# Easy_RFPA_RevC.net
KiCad netlist of a schematic drawn in EAGLE
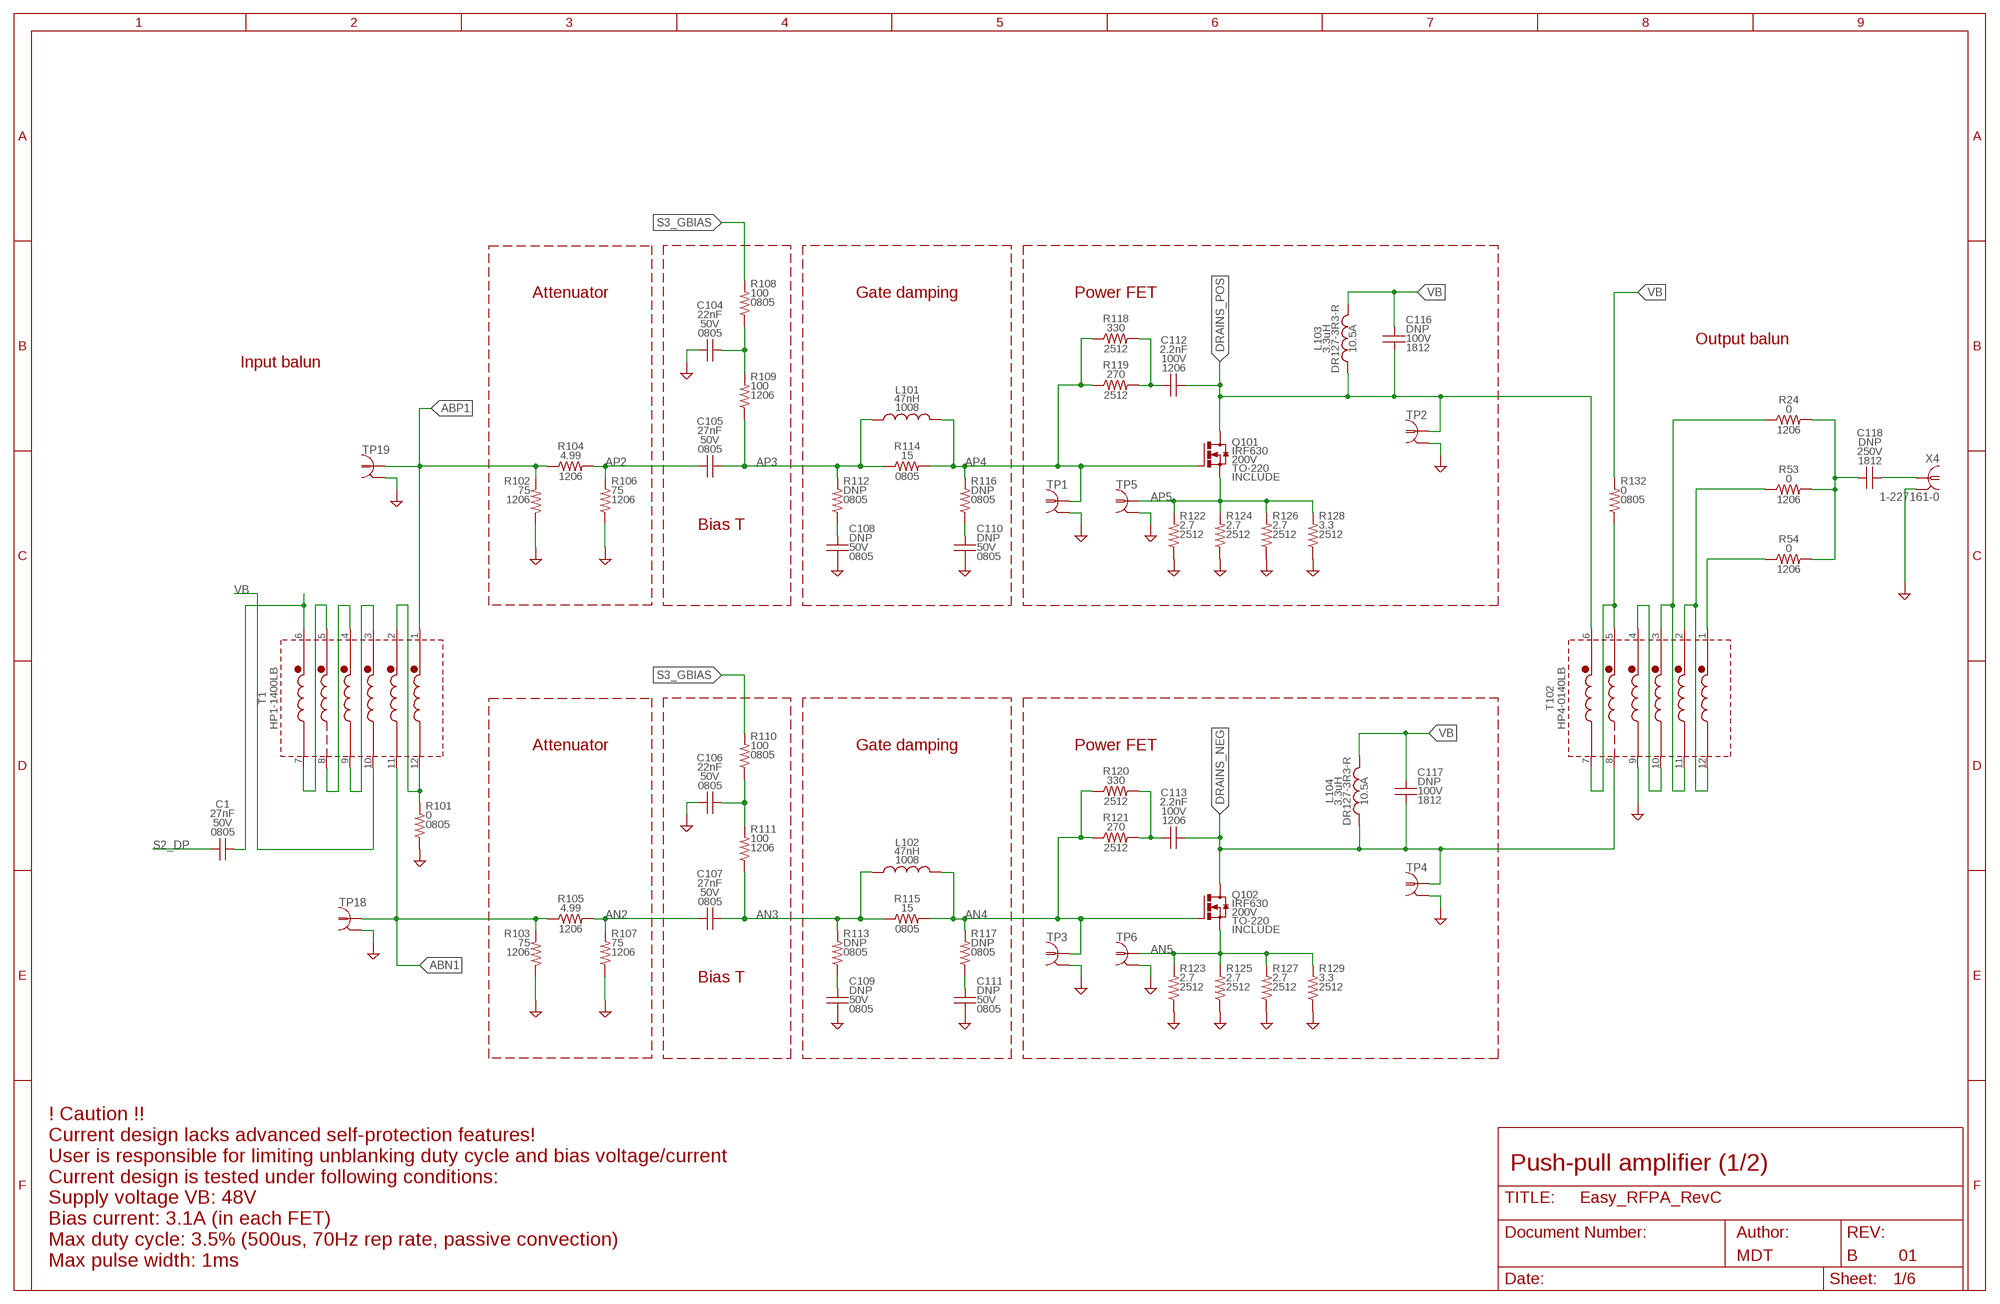
[diagram p0: schematic, sheet 1]
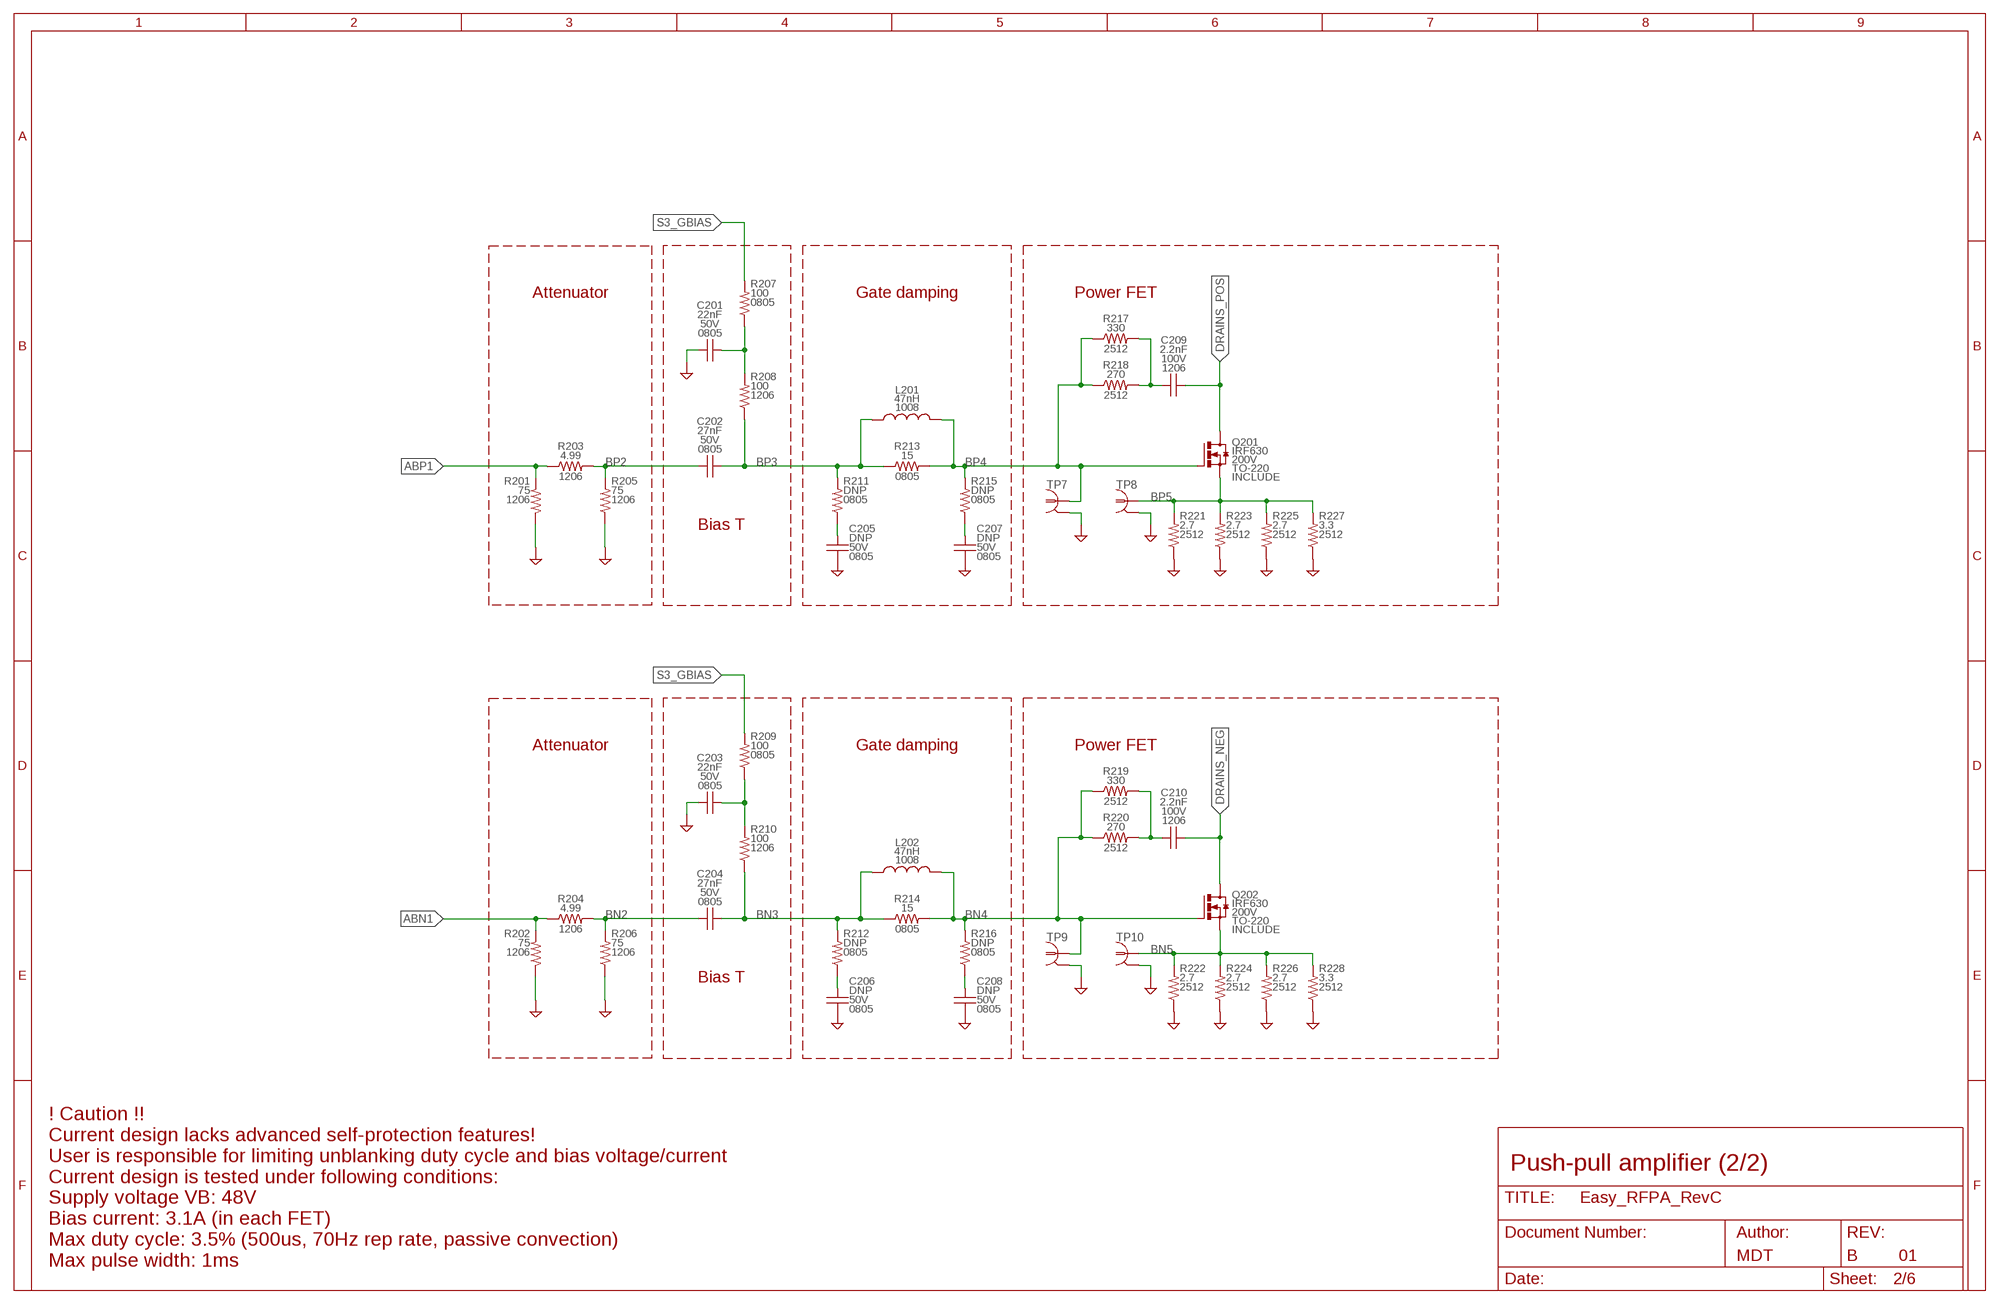
[diagram p1: schematic, sheet 2]
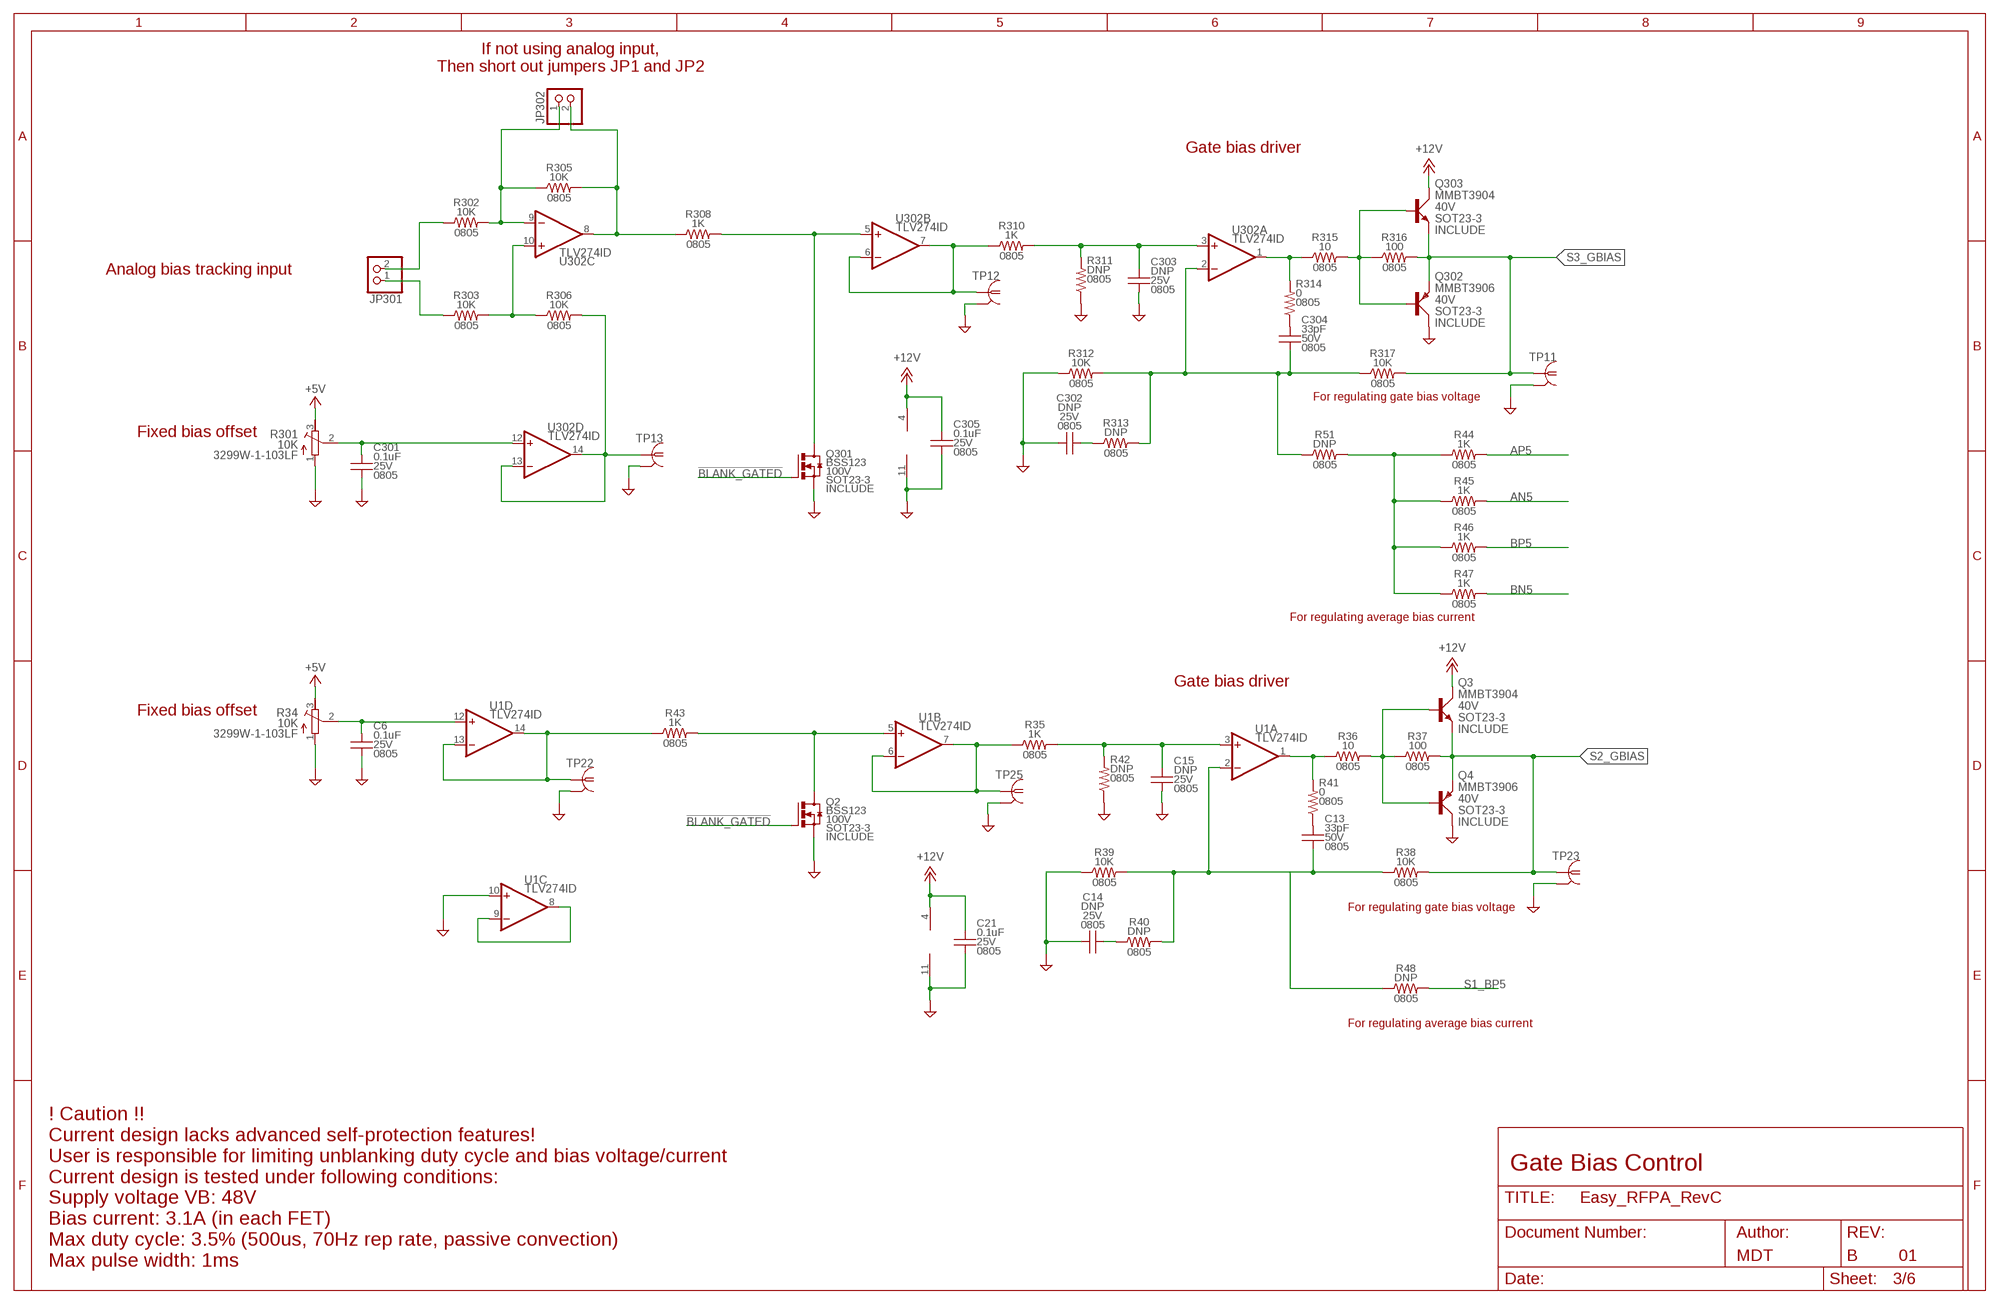
[diagram p2: schematic, sheet 3]
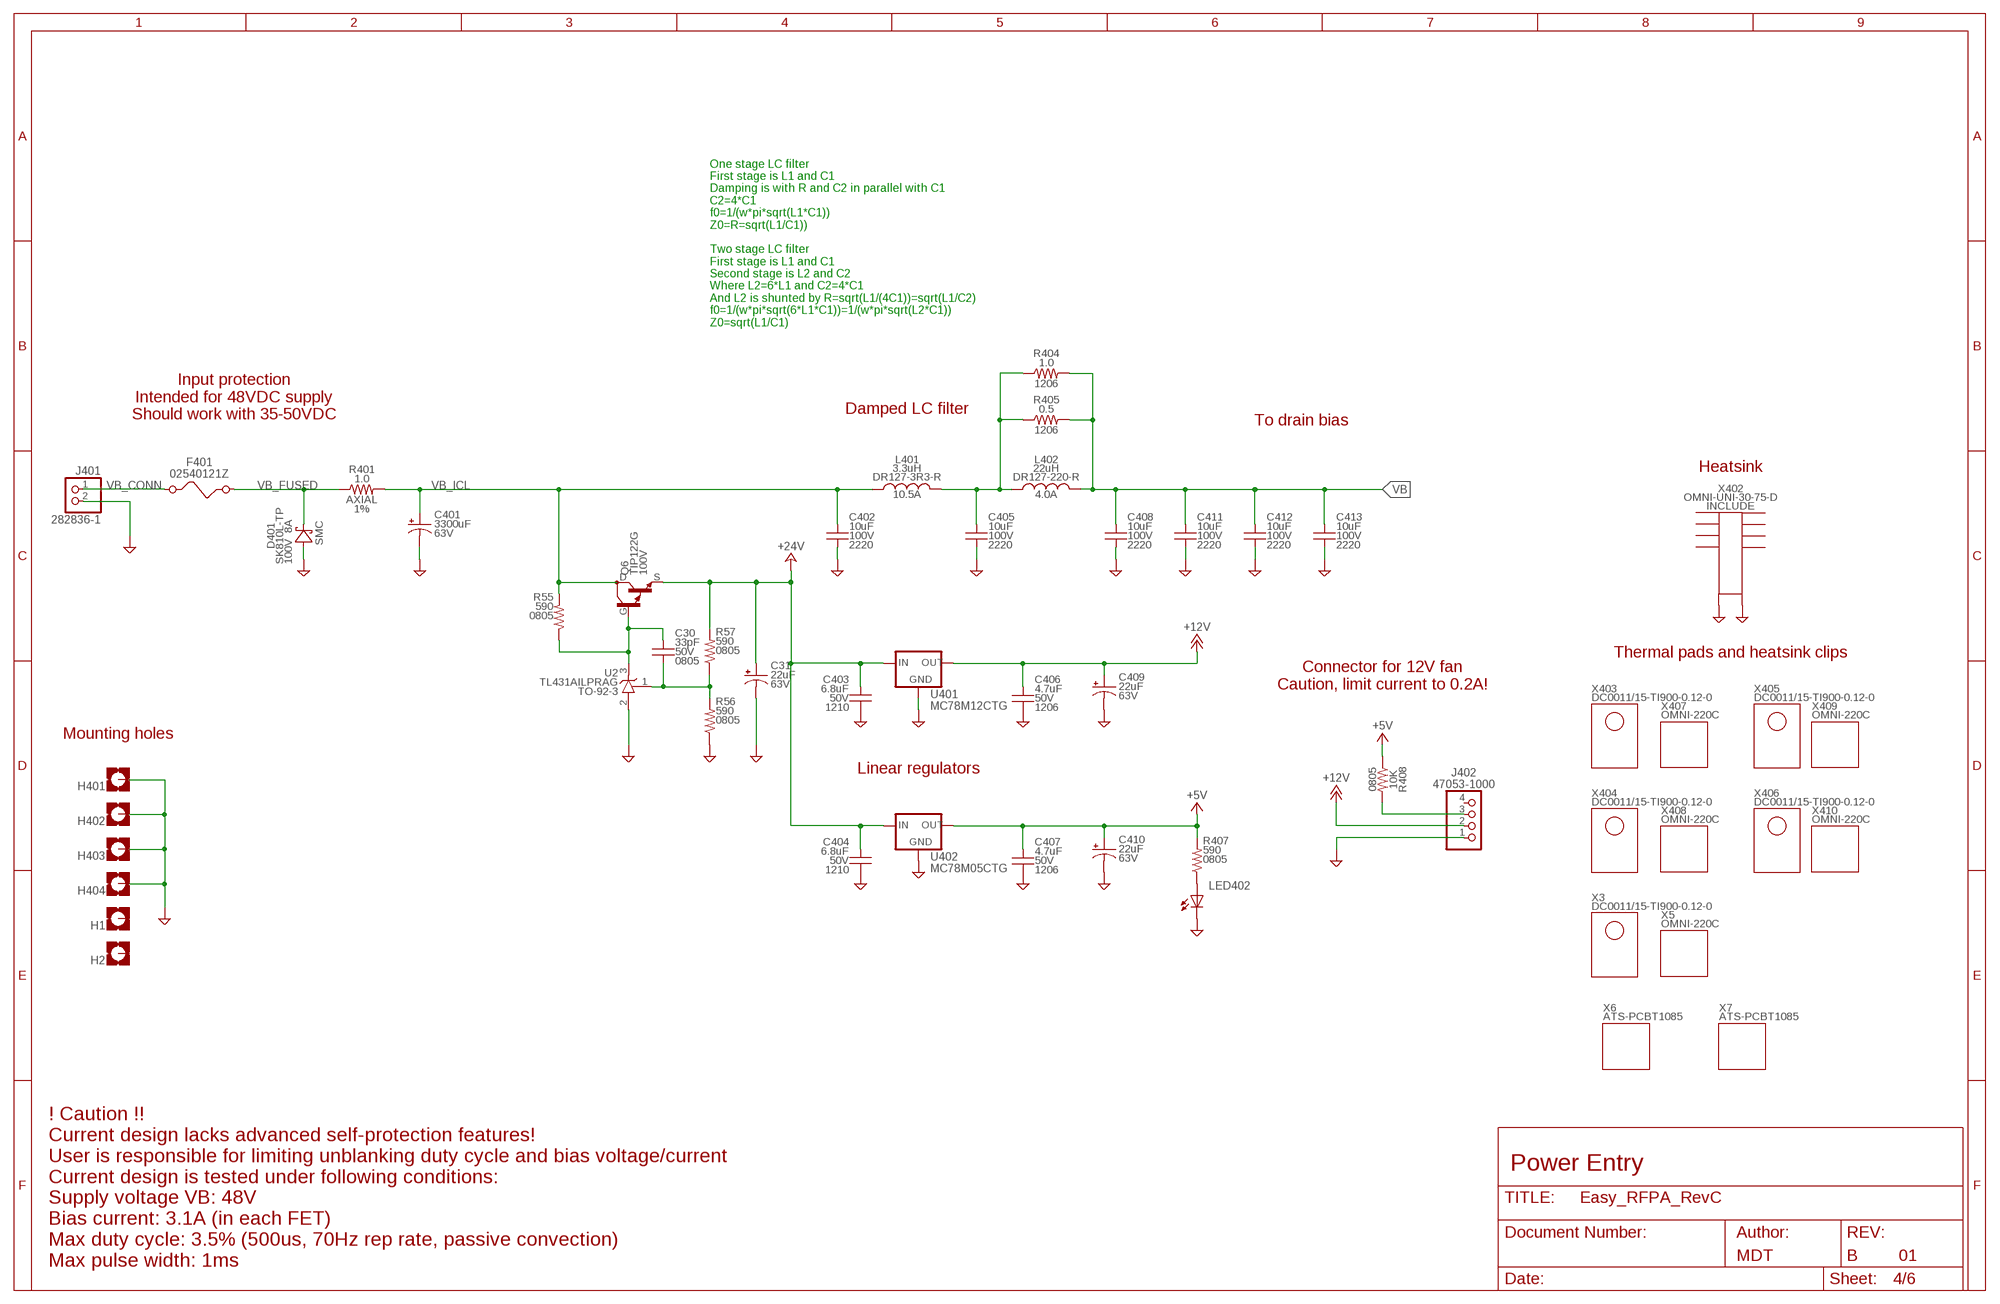
[diagram p3: schematic, sheet 4]
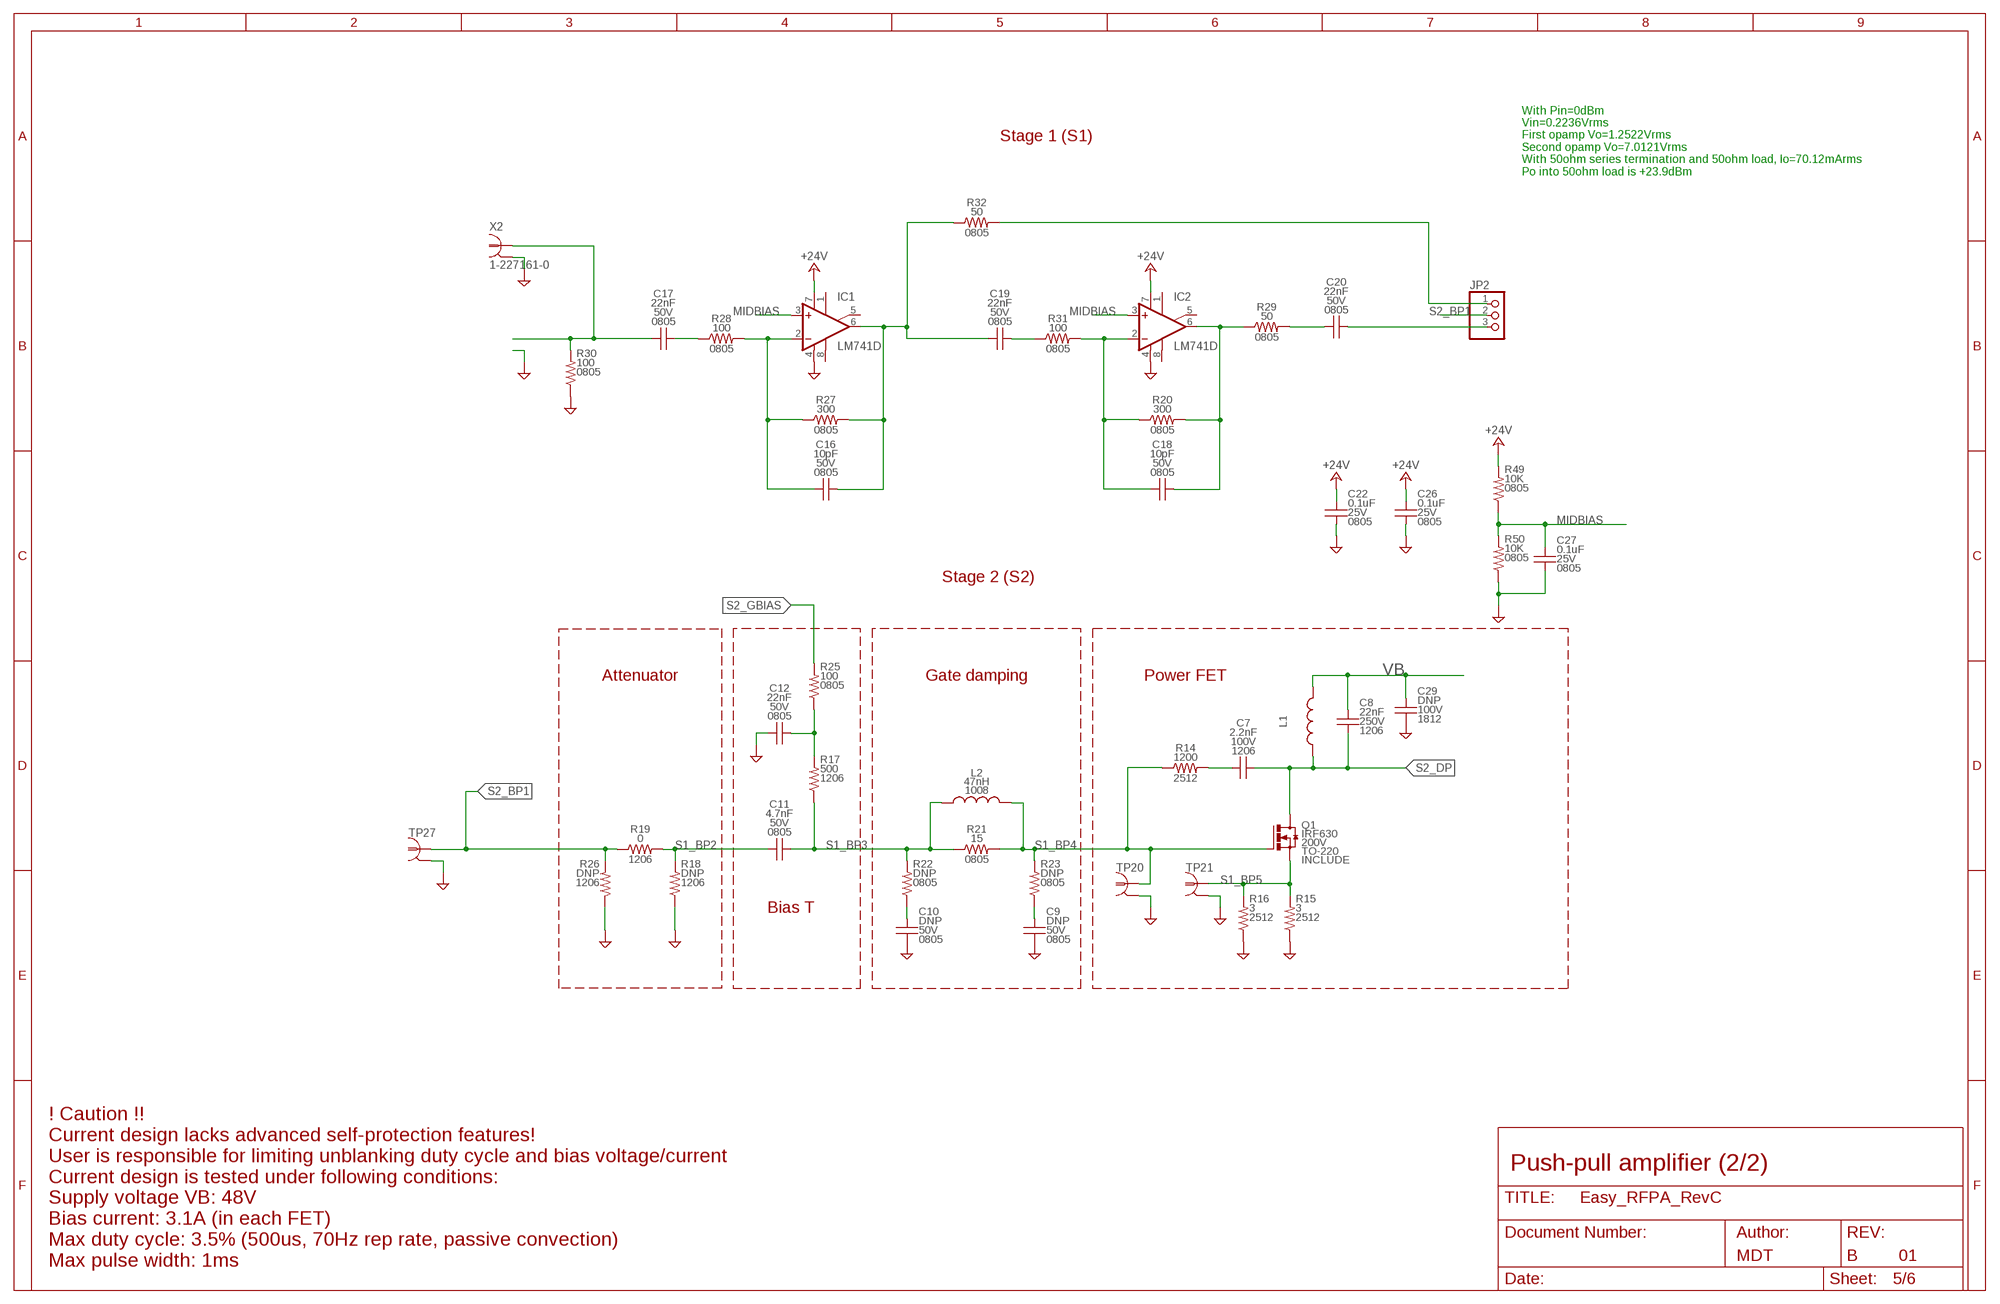
[diagram p4: schematic, sheet 5]
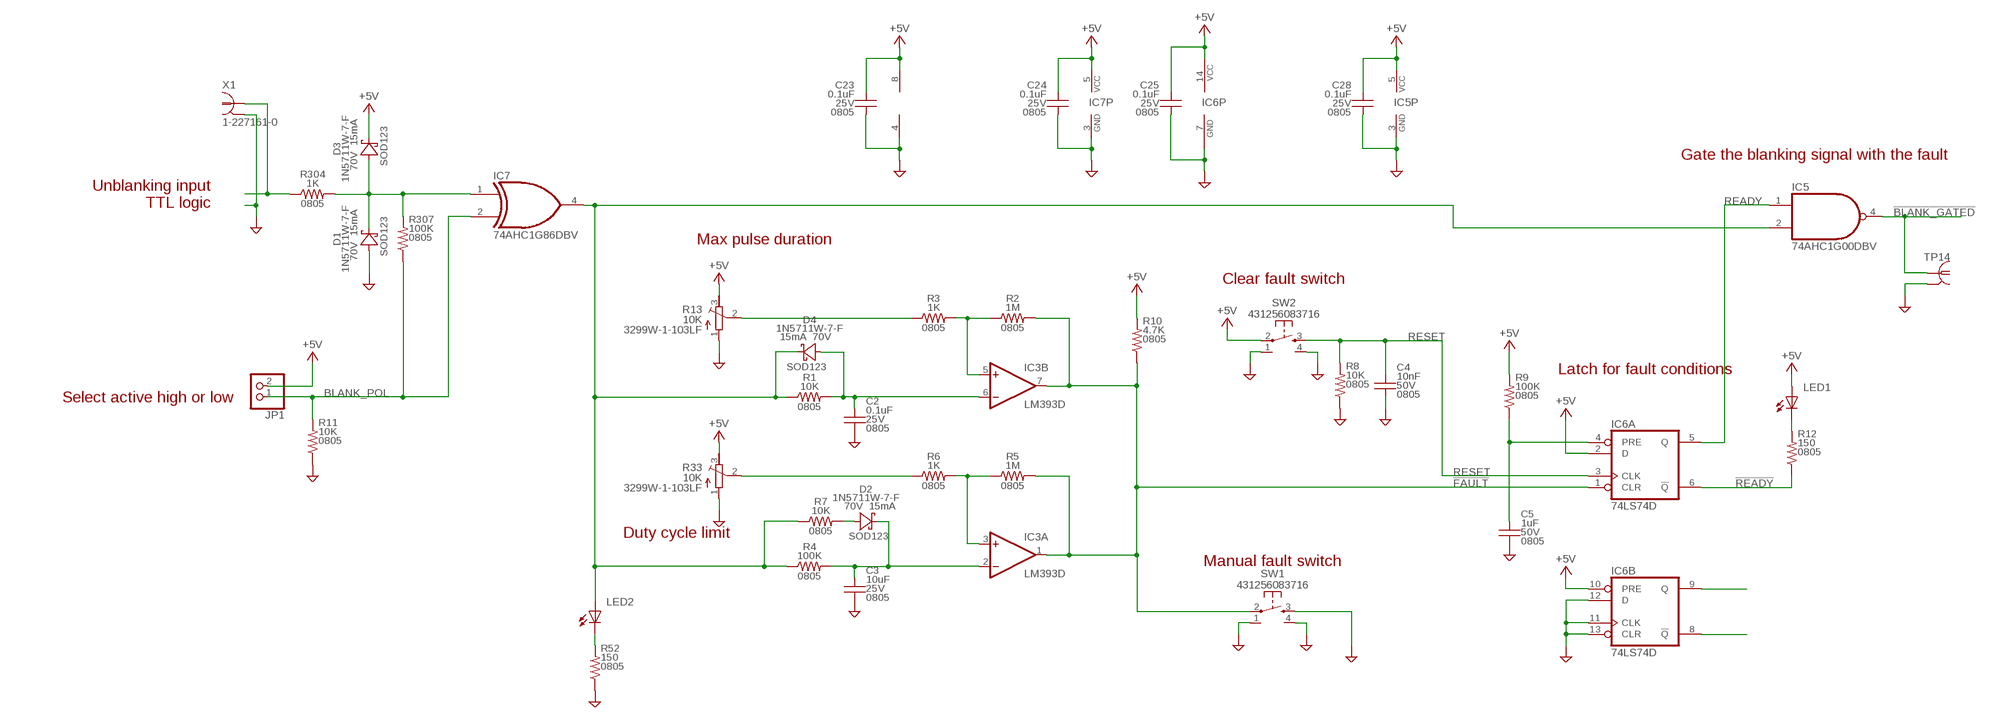
[diagram p5: schematic, sheet 6]

(export (version "E")
  (design (tool "Eeschema 10.0.6"))
  (components
    (comp (ref "C2")
      (value "0.1uF")
      (footprint "eagle-import:0805_IPC-7351B")
      (fields (field (name "VOLTAGE") "25V"))
      (libsource (lib "eagle-import") (part "C0805_IPCGEN"))
    )
    (comp (ref "C3")
      (value "10uF")
      (footprint "eagle-import:0805_IPC-7351B")
      (fields (field (name "VOLTAGE") "25V"))
      (libsource (lib "eagle-import") (part "C0805_IPCGEN"))
    )
    (comp (ref "C4")
      (value "10nF")
      (footprint "eagle-import:0805_IPC-7351B")
      (fields (field (name "VOLTAGE") "50V"))
      (libsource (lib "eagle-import") (part "C0805_IPCGEN"))
    )
    (comp (ref "C5")
      (value "1uF")
      (footprint "eagle-import:0805_IPC-7351B")
      (fields (field (name "VOLTAGE") "50V"))
      (libsource (lib "eagle-import") (part "C0805_IPCGEN"))
    )
    (comp (ref "C23")
      (value "0.1uF")
      (footprint "eagle-import:0805_IPC-7351B")
      (fields (field (name "VOLTAGE") "25V"))
      (libsource (lib "eagle-import") (part "C0805_IPCGEN"))
    )
    (comp (ref "C24")
      (value "0.1uF")
      (footprint "eagle-import:0805_IPC-7351B")
      (fields (field (name "VOLTAGE") "25V"))
      (libsource (lib "eagle-import") (part "C0805_IPCGEN"))
    )
    (comp (ref "C25")
      (value "0.1uF")
      (footprint "eagle-import:0805_IPC-7351B")
      (fields (field (name "VOLTAGE") "25V"))
      (libsource (lib "eagle-import") (part "C0805_IPCGEN"))
    )
    (comp (ref "C28")
      (value "0.1uF")
      (footprint "eagle-import:0805_IPC-7351B")
      (fields (field (name "VOLTAGE") "25V"))
      (libsource (lib "eagle-import") (part "C0805_IPCGEN"))
    )
    (comp (ref "D1")
      (value "D-SCHOTTKY1N5711W-7-FSOD123")
      (footprint "eagle-import:SOD123")
      (fields (field (name "PARTNO") "1N5711W-7-F") (field (name "VOLTAGE") "70V"))
      (libsource (lib "eagle-import") (part "D-SCHOTTKYSOD1231N5711W-7-F"))
    )
    (comp (ref "D2")
      (value "D-SCHOTTKY1N5711W-7-FSOD123")
      (footprint "eagle-import:SOD123")
      (fields (field (name "PARTNO") "1N5711W-7-F") (field (name "VOLTAGE") "70V"))
      (libsource (lib "eagle-import") (part "D-SCHOTTKYSOD1231N5711W-7-F"))
    )
    (comp (ref "D3")
      (value "D-SCHOTTKY1N5711W-7-FSOD123")
      (footprint "eagle-import:SOD123")
      (fields (field (name "PARTNO") "1N5711W-7-F") (field (name "VOLTAGE") "70V"))
      (libsource (lib "eagle-import") (part "D-SCHOTTKYSOD1231N5711W-7-F"))
    )
    (comp (ref "D4")
      (value "D-SCHOTTKY1N5711W-7-FSOD123")
      (footprint "eagle-import:SOD123")
      (fields (field (name "PARTNO") "1N5711W-7-F") (field (name "VOLTAGE") "70V"))
      (libsource (lib "eagle-import") (part "D-SCHOTTKYSOD1231N5711W-7-F"))
    )
    (comp (ref "IC3")
      (value "LM393D")
      (footprint "eagle-import:SO08")
      (libsource (lib "eagle-import") (part "LM393D"))
    )
    (comp (ref "IC5")
      (value "74AHC1G00DBV")
      (footprint "eagle-import:SOT23-5")
      (libsource (lib "eagle-import") (part "741G00DBVAHC"))
    )
    (comp (ref "IC6")
      (value "74LS74D")
      (footprint "eagle-import:SO14")
      (libsource (lib "eagle-import") (part "7474DLS"))
    )
    (comp (ref "IC7")
      (value "74AHC1G86DBV")
      (footprint "eagle-import:SOT23-5")
      (libsource (lib "eagle-import") (part "741G86DBVAHC"))
    )
    (comp (ref "JP1")
      (value "PINHD-1X2")
      (footprint "eagle-import:1X02")
      (libsource (lib "eagle-import") (part "PINHD-1X2"))
    )
    (comp (ref "LED1")
      (value "LEDT1_3/4_RA")
      (footprint "eagle-import:LED_5MM_RA")
      (libsource (lib "eagle-import") (part "LEDT1_3/4_RA"))
    )
    (comp (ref "LED2")
      (value "LEDT1_3/4_RA")
      (footprint "eagle-import:LED_5MM_RA")
      (libsource (lib "eagle-import") (part "LEDT1_3/4_RA"))
    )
    (comp (ref "R1")
      (value "10K")
      (footprint "eagle-import:0805_IPC-7351B")
      (libsource (lib "eagle-import") (part "R900805_IPCGEN"))
    )
    (comp (ref "R2")
      (value "1M")
      (footprint "eagle-import:0805_IPC-7351B")
      (libsource (lib "eagle-import") (part "R900805_IPCGEN"))
    )
    (comp (ref "R3")
      (value "1K")
      (footprint "eagle-import:0805_IPC-7351B")
      (libsource (lib "eagle-import") (part "R900805_IPCGEN"))
    )
    (comp (ref "R4")
      (value "100K")
      (footprint "eagle-import:0805_IPC-7351B")
      (libsource (lib "eagle-import") (part "R900805_IPCGEN"))
    )
    (comp (ref "R5")
      (value "1M")
      (footprint "eagle-import:0805_IPC-7351B")
      (libsource (lib "eagle-import") (part "R900805_IPCGEN"))
    )
    (comp (ref "R6")
      (value "1K")
      (footprint "eagle-import:0805_IPC-7351B")
      (libsource (lib "eagle-import") (part "R900805_IPCGEN"))
    )
    (comp (ref "R7")
      (value "10K")
      (footprint "eagle-import:0805_IPC-7351B")
      (libsource (lib "eagle-import") (part "R900805_IPCGEN"))
    )
    (comp (ref "R8")
      (value "10K")
      (footprint "eagle-import:0805_IPC-7351B")
      (libsource (lib "eagle-import") (part "R0805_IPCGEN"))
    )
    (comp (ref "R9")
      (value "100K")
      (footprint "eagle-import:0805_IPC-7351B")
      (libsource (lib "eagle-import") (part "R0805_IPCGEN"))
    )
    (comp (ref "R10")
      (value "4.7K")
      (footprint "eagle-import:0805_IPC-7351B")
      (libsource (lib "eagle-import") (part "R0805_IPCGEN"))
    )
    (comp (ref "R11")
      (value "10K")
      (footprint "eagle-import:0805_IPC-7351B")
      (libsource (lib "eagle-import") (part "R0805_IPCGEN"))
    )
    (comp (ref "R12")
      (value "150")
      (footprint "eagle-import:0805_IPC-7351B")
      (libsource (lib "eagle-import") (part "R0805_IPCGEN"))
    )
    (comp (ref "R13")
      (value "10K")
      (footprint "eagle-import:RTRIM3299W")
      (fields (field (name "PARTNO") "3299W-1-103LF") (field (name "POWER") "0.5W"))
      (libsource (lib "eagle-import") (part "RTRIM3299WRTRIM-10K-10%-3299W-0.5W"))
    )
    (comp (ref "R33")
      (value "10K")
      (footprint "eagle-import:RTRIM3299W")
      (fields (field (name "PARTNO") "3299W-1-103LF") (field (name "POWER") "0.5W"))
      (libsource (lib "eagle-import") (part "RTRIM3299WRTRIM-10K-10%-3299W-0.5W"))
    )
    (comp (ref "R52")
      (value "150")
      (footprint "eagle-import:0805_IPC-7351B")
      (libsource (lib "eagle-import") (part "R0805_IPCGEN"))
    )
    (comp (ref "R304")
      (value "1K")
      (footprint "eagle-import:0805_IPC-7351B")
      (libsource (lib "eagle-import") (part "R900805_IPCGEN"))
    )
    (comp (ref "R307")
      (value "100K")
      (footprint "eagle-import:0805_IPC-7351B")
      (libsource (lib "eagle-import") (part "R0805_IPCGEN"))
    )
    (comp (ref "SW1")
      (value "SPST_NO_TACT_RA431256083716431256083716")
      (footprint "eagle-import:431256083716")
      (fields (field (name "PARTNO") "431256083716"))
      (libsource (lib "eagle-import") (part "SPST_NO_TACT_RA431256083716431256083716"))
    )
    (comp (ref "SW2")
      (value "SPST_NO_TACT_RA431256083716431256083716")
      (footprint "eagle-import:431256083716")
      (fields (field (name "PARTNO") "431256083716"))
      (libsource (lib "eagle-import") (part "SPST_NO_TACT_RA431256083716431256083716"))
    )
    (comp (ref "TP14")
      (value "PROBE_TPTP_5MM")
      (footprint "eagle-import:PROBE_TP_5MM")
      (libsource (lib "eagle-import") (part "PROBE_TPTP_5MM"))
    )
    (comp (ref "X1")
      (value "1-227161-0")
      (footprint "eagle-import:AMP_227161")
      (fields (field (name "MF") "TYCO ELECTRONICS") (field (name "MPN") "1-227161"))
      (libsource (lib "eagle-import") (part "?2271611--0"))
    )
    (comp (ref "C6")
      (value "0.1uF")
      (footprint "eagle-import:0805_IPC-7351B")
      (fields (field (name "VOLTAGE") "25V"))
      (libsource (lib "eagle-import") (part "C0805_IPCGEN"))
    )
    (comp (ref "C13")
      (value "33pF")
      (footprint "eagle-import:0805_IPC-7351B")
      (fields (field (name "VOLTAGE") "50V"))
      (libsource (lib "eagle-import") (part "C0805_IPCGEN"))
    )
    (comp (ref "C14")
      (value "DNP")
      (footprint "eagle-import:0805_IPC-7351B")
      (fields (field (name "PACKAGE") "0805") (field (name "BOM") "EXCLUDE") (field (name "VOLTAGE") "25V"))
      (libsource (lib "eagle-import") (part "C0805_IPCGEN"))
    )
    (comp (ref "C15")
      (value "DNP")
      (footprint "eagle-import:0805_IPC-7351B")
      (fields (field (name "BOM") "EXCLUDE") (field (name "VOLTAGE") "25V"))
      (libsource (lib "eagle-import") (part "C0805_IPCGEN"))
    )
    (comp (ref "C21")
      (value "0.1uF")
      (footprint "eagle-import:0805_IPC-7351B")
      (fields (field (name "VOLTAGE") "25V"))
      (libsource (lib "eagle-import") (part "C0805_IPCGEN"))
    )
    (comp (ref "C301")
      (value "0.1uF")
      (footprint "eagle-import:0805_IPC-7351B")
      (fields (field (name "VOLTAGE") "25V"))
      (libsource (lib "eagle-import") (part "C0805_IPCGEN"))
    )
    (comp (ref "C302")
      (value "DNP")
      (footprint "eagle-import:0805_IPC-7351B")
      (fields (field (name "PACKAGE") "0805") (field (name "BOM") "EXCLUDE") (field (name "VOLTAGE") "25V"))
      (libsource (lib "eagle-import") (part "C0805_IPCGEN"))
    )
    (comp (ref "C303")
      (value "DNP")
      (footprint "eagle-import:0805_IPC-7351B")
      (fields (field (name "BOM") "EXCLUDE") (field (name "VOLTAGE") "25V"))
      (libsource (lib "eagle-import") (part "C0805_IPCGEN"))
    )
    (comp (ref "C304")
      (value "33pF")
      (footprint "eagle-import:0805_IPC-7351B")
      (fields (field (name "VOLTAGE") "50V"))
      (libsource (lib "eagle-import") (part "C0805_IPCGEN"))
    )
    (comp (ref "C305")
      (value "0.1uF")
      (footprint "eagle-import:0805_IPC-7351B")
      (fields (field (name "VOLTAGE") "25V"))
      (libsource (lib "eagle-import") (part "C0805_IPCGEN"))
    )
    (comp (ref "JP301")
      (value "PINHD-1X2")
      (footprint "eagle-import:1X02")
      (libsource (lib "eagle-import") (part "PINHD-1X2"))
    )
    (comp (ref "JP302")
      (value "PINHD-1X2")
      (footprint "eagle-import:1X02")
      (libsource (lib "eagle-import") (part "PINHD-1X2"))
    )
    (comp (ref "Q2")
      (value "MOSFET_NBSS123SOT23")
      (footprint "eagle-import:SOT23R_INFINEON")
      (fields (field (name "PARTNO") "BSS123-7-F") (field (name "VOLTAGE") "100V"))
      (libsource (lib "eagle-import") (part "MOSFET_NSOT23BSS123"))
    )
    (comp (ref "Q3")
      (value "NPNMMBT3904SOT23_BEC")
      (footprint "eagle-import:SOT23R_INFINEON")
      (fields (field (name "PARTNO") "MMBT3904,215") (field (name "VOLTAGE") "40V"))
      (libsource (lib "eagle-import") (part "NPNSOT23_BECMMBT3904"))
    )
    (comp (ref "Q4")
      (value "PNPSOT23_BEC")
      (footprint "eagle-import:SOT23R_INFINEON")
      (fields (field (name "VOLTAGE") "40V") (field (name "PARTNO") "PMBT3906,215"))
      (libsource (lib "eagle-import") (part "PNPSOT23_BEC"))
    )
    (comp (ref "Q301")
      (value "MOSFET_NBSS123SOT23")
      (footprint "eagle-import:SOT23R_INFINEON")
      (fields (field (name "PARTNO") "BSS123-7-F") (field (name "VOLTAGE") "100V"))
      (libsource (lib "eagle-import") (part "MOSFET_NSOT23BSS123"))
    )
    (comp (ref "Q302")
      (value "PNPSOT23_BEC")
      (footprint "eagle-import:SOT23R_INFINEON")
      (fields (field (name "VOLTAGE") "40V") (field (name "PARTNO") "PMBT3906,215"))
      (libsource (lib "eagle-import") (part "PNPSOT23_BEC"))
    )
    (comp (ref "Q303")
      (value "NPNMMBT3904SOT23_BEC")
      (footprint "eagle-import:SOT23R_INFINEON")
      (fields (field (name "PARTNO") "MMBT3904,215") (field (name "VOLTAGE") "40V"))
      (libsource (lib "eagle-import") (part "NPNSOT23_BECMMBT3904"))
    )
    (comp (ref "R34")
      (value "10K")
      (footprint "eagle-import:RTRIM3299W")
      (fields (field (name "PARTNO") "3299W-1-103LF") (field (name "POWER") "0.5W"))
      (libsource (lib "eagle-import") (part "RTRIM3299WRTRIM-10K-10%-3299W-0.5W"))
    )
    (comp (ref "R35")
      (value "1K")
      (footprint "eagle-import:0805_IPC-7351B")
      (libsource (lib "eagle-import") (part "R900805_IPCGEN"))
    )
    (comp (ref "R36")
      (value "10")
      (footprint "eagle-import:0805_IPC-7351B")
      (libsource (lib "eagle-import") (part "R900805_IPCGEN"))
    )
    (comp (ref "R37")
      (value "100")
      (footprint "eagle-import:0805_IPC-7351B")
      (libsource (lib "eagle-import") (part "R900805_IPCGEN"))
    )
    (comp (ref "R38")
      (value "10K")
      (footprint "eagle-import:0805_IPC-7351B")
      (libsource (lib "eagle-import") (part "R900805_IPCGEN"))
    )
    (comp (ref "R39")
      (value "10K")
      (footprint "eagle-import:0805_IPC-7351B")
      (libsource (lib "eagle-import") (part "R900805_IPCGEN"))
    )
    (comp (ref "R40")
      (value "DNP")
      (footprint "eagle-import:0805_IPC-7351B")
      (fields (field (name "BOM") "EXCLUDE"))
      (libsource (lib "eagle-import") (part "R900805_IPCGEN"))
    )
    (comp (ref "R41")
      (value "0")
      (footprint "eagle-import:0805_IPC-7351B")
      (libsource (lib "eagle-import") (part "R0805_IPCGEN"))
    )
    (comp (ref "R42")
      (value "DNP")
      (footprint "eagle-import:0805_IPC-7351B")
      (fields (field (name "BOM") "EXCLUDE"))
      (libsource (lib "eagle-import") (part "R0805_IPCGEN"))
    )
    (comp (ref "R43")
      (value "1K")
      (footprint "eagle-import:0805_IPC-7351B")
      (libsource (lib "eagle-import") (part "R900805_IPCGEN"))
    )
    (comp (ref "R44")
      (value "1K")
      (footprint "eagle-import:0805_IPC-7351B")
      (fields (field (name "BOM") "EXCLUDE"))
      (libsource (lib "eagle-import") (part "R900805_IPCGEN"))
    )
    (comp (ref "R45")
      (value "1K")
      (footprint "eagle-import:0805_IPC-7351B")
      (fields (field (name "BOM") "EXCLUDE"))
      (libsource (lib "eagle-import") (part "R900805_IPCGEN"))
    )
    (comp (ref "R46")
      (value "1K")
      (footprint "eagle-import:0805_IPC-7351B")
      (fields (field (name "BOM") "EXCLUDE"))
      (libsource (lib "eagle-import") (part "R900805_IPCGEN"))
    )
    (comp (ref "R47")
      (value "1K")
      (footprint "eagle-import:0805_IPC-7351B")
      (fields (field (name "BOM") "EXCLUDE"))
      (libsource (lib "eagle-import") (part "R900805_IPCGEN"))
    )
    (comp (ref "R48")
      (value "DNP")
      (footprint "eagle-import:0805_IPC-7351B")
      (fields (field (name "BOM") "EXCLUDE"))
      (libsource (lib "eagle-import") (part "R900805_IPCGEN"))
    )
    (comp (ref "R51")
      (value "DNP")
      (footprint "eagle-import:0805_IPC-7351B")
      (fields (field (name "BOM") "EXCLUDE"))
      (libsource (lib "eagle-import") (part "R900805_IPCGEN"))
    )
    (comp (ref "R301")
      (value "10K")
      (footprint "eagle-import:RTRIM3299W")
      (fields (field (name "PARTNO") "3299W-1-103LF") (field (name "POWER") "0.5W"))
      (libsource (lib "eagle-import") (part "RTRIM3299WRTRIM-10K-10%-3299W-0.5W"))
    )
    (comp (ref "R302")
      (value "10K")
      (footprint "eagle-import:0805_IPC-7351B")
      (libsource (lib "eagle-import") (part "R900805_IPCGEN"))
    )
    (comp (ref "R303")
      (value "10K")
      (footprint "eagle-import:0805_IPC-7351B")
      (libsource (lib "eagle-import") (part "R900805_IPCGEN"))
    )
    (comp (ref "R305")
      (value "10K")
      (footprint "eagle-import:0805_IPC-7351B")
      (libsource (lib "eagle-import") (part "R900805_IPCGEN"))
    )
    (comp (ref "R306")
      (value "10K")
      (footprint "eagle-import:0805_IPC-7351B")
      (libsource (lib "eagle-import") (part "R900805_IPCGEN"))
    )
    (comp (ref "R308")
      (value "1K")
      (footprint "eagle-import:0805_IPC-7351B")
      (libsource (lib "eagle-import") (part "R900805_IPCGEN"))
    )
    (comp (ref "R310")
      (value "1K")
      (footprint "eagle-import:0805_IPC-7351B")
      (libsource (lib "eagle-import") (part "R900805_IPCGEN"))
    )
    (comp (ref "R311")
      (value "DNP")
      (footprint "eagle-import:0805_IPC-7351B")
      (fields (field (name "BOM") "EXCLUDE"))
      (libsource (lib "eagle-import") (part "R0805_IPCGEN"))
    )
    (comp (ref "R312")
      (value "10K")
      (footprint "eagle-import:0805_IPC-7351B")
      (libsource (lib "eagle-import") (part "R900805_IPCGEN"))
    )
    (comp (ref "R313")
      (value "DNP")
      (footprint "eagle-import:0805_IPC-7351B")
      (fields (field (name "BOM") "EXCLUDE"))
      (libsource (lib "eagle-import") (part "R900805_IPCGEN"))
    )
    (comp (ref "R314")
      (value "0")
      (footprint "eagle-import:0805_IPC-7351B")
      (libsource (lib "eagle-import") (part "R0805_IPCGEN"))
    )
    (comp (ref "R315")
      (value "10")
      (footprint "eagle-import:0805_IPC-7351B")
      (libsource (lib "eagle-import") (part "R900805_IPCGEN"))
    )
    (comp (ref "R316")
      (value "100")
      (footprint "eagle-import:0805_IPC-7351B")
      (libsource (lib "eagle-import") (part "R900805_IPCGEN"))
    )
    (comp (ref "R317")
      (value "10K")
      (footprint "eagle-import:0805_IPC-7351B")
      (libsource (lib "eagle-import") (part "R900805_IPCGEN"))
    )
    (comp (ref "TP11")
      (value "PROBE_TPTP_5MM")
      (footprint "eagle-import:PROBE_TP_5MM")
      (libsource (lib "eagle-import") (part "PROBE_TPTP_5MM"))
    )
    (comp (ref "TP12")
      (value "PROBE_TPTP_5MM")
      (footprint "eagle-import:PROBE_TP_5MM")
      (libsource (lib "eagle-import") (part "PROBE_TPTP_5MM"))
    )
    (comp (ref "TP13")
      (value "PROBE_TPTP_5MM")
      (footprint "eagle-import:PROBE_TP_5MM")
      (libsource (lib "eagle-import") (part "PROBE_TPTP_5MM"))
    )
    (comp (ref "TP22")
      (value "PROBE_TPTP_5MM")
      (footprint "eagle-import:PROBE_TP_5MM")
      (libsource (lib "eagle-import") (part "PROBE_TPTP_5MM"))
    )
    (comp (ref "TP23")
      (value "PROBE_TPTP_5MM")
      (footprint "eagle-import:PROBE_TP_5MM")
      (libsource (lib "eagle-import") (part "PROBE_TPTP_5MM"))
    )
    (comp (ref "TP25")
      (value "PROBE_TPTP_5MM")
      (footprint "eagle-import:PROBE_TP_5MM")
      (libsource (lib "eagle-import") (part "PROBE_TPTP_5MM"))
    )
    (comp (ref "U1")
      (value "OPAMP_QUADTLV274IDSOIC14")
      (footprint "eagle-import:SO14")
      (fields (field (name "PARTNO") "TLV274ID"))
      (libsource (lib "eagle-import") (part "OPAMP_QUADSOIC14TLV274ID"))
    )
    (comp (ref "U302")
      (value "OPAMP_QUADTLV274IDSOIC14")
      (footprint "eagle-import:SO14")
      (fields (field (name "PARTNO") "TLV274ID"))
      (libsource (lib "eagle-import") (part "OPAMP_QUADSOIC14TLV274ID"))
    )
    (comp (ref "C1")
      (value "27nF")
      (footprint "eagle-import:0805_IPC-7351B")
      (fields (field (name "PACKAGE") "0805") (field (name "VOLTAGE") "50V"))
      (libsource (lib "eagle-import") (part "C0805_IPCGEN"))
    )
    (comp (ref "C104")
      (value "22nF")
      (footprint "eagle-import:0805_IPC-7351B")
      (fields (field (name "BOM") "INCLUDE") (field (name "PACKAGE") "0805") (field (name "VOLTAGE") "50V"))
      (libsource (lib "eagle-import") (part "C0805_IPCGEN"))
    )
    (comp (ref "C105")
      (value "27nF")
      (footprint "eagle-import:0805_IPC-7351B")
      (fields (field (name "PACKAGE") "0805") (field (name "VOLTAGE") "50V"))
      (libsource (lib "eagle-import") (part "C0805_IPCGEN"))
    )
    (comp (ref "C106")
      (value "22nF")
      (footprint "eagle-import:0805_IPC-7351B")
      (fields (field (name "PACKAGE") "0805") (field (name "VOLTAGE") "50V"))
      (libsource (lib "eagle-import") (part "C0805_IPCGEN"))
    )
    (comp (ref "C107")
      (value "27nF")
      (footprint "eagle-import:0805_IPC-7351B")
      (fields (field (name "PACKAGE") "0805") (field (name "VOLTAGE") "50V"))
      (libsource (lib "eagle-import") (part "C0805_IPCGEN"))
    )
    (comp (ref "C108")
      (value "DNP")
      (footprint "eagle-import:0805_IPC-7351B")
      (fields (field (name "BOM") "EXCLUDE") (field (name "VOLTAGE") "50V"))
      (libsource (lib "eagle-import") (part "C0805_IPCGEN"))
    )
    (comp (ref "C109")
      (value "DNP")
      (footprint "eagle-import:0805_IPC-7351B")
      (fields (field (name "BOM") "EXCLUDE") (field (name "VOLTAGE") "50V"))
      (libsource (lib "eagle-import") (part "C0805_IPCGEN"))
    )
    (comp (ref "C110")
      (value "DNP")
      (footprint "eagle-import:0805_IPC-7351B")
      (fields (field (name "BOM") "EXCLUDE") (field (name "VOLTAGE") "50V"))
      (libsource (lib "eagle-import") (part "C0805_IPCGEN"))
    )
    (comp (ref "C111")
      (value "DNP")
      (footprint "eagle-import:0805_IPC-7351B")
      (fields (field (name "BOM") "EXCLUDE") (field (name "VOLTAGE") "50V"))
      (libsource (lib "eagle-import") (part "C0805_IPCGEN"))
    )
    (comp (ref "C112")
      (value "2.2nF")
      (footprint "eagle-import:C1206")
      (fields (field (name "PACKAGE") "1206") (field (name "VOLTAGE") "100V"))
      (libsource (lib "eagle-import") (part "CC1206GEN"))
    )
    (comp (ref "C113")
      (value "2.2nF")
      (footprint "eagle-import:C1206")
      (fields (field (name "PACKAGE") "1206") (field (name "VOLTAGE") "100V"))
      (libsource (lib "eagle-import") (part "CC1206GEN"))
    )
    (comp (ref "C116")
      (value "DNP")
      (footprint "eagle-import:C1812")
      (fields (field (name "BOM") "EXCLUDE") (field (name "VOLTAGE") "100V"))
      (libsource (lib "eagle-import") (part "CC1812GEN"))
    )
    (comp (ref "C117")
      (value "DNP")
      (footprint "eagle-import:C1812")
      (fields (field (name "BOM") "EXCLUDE") (field (name "VOLTAGE") "100V"))
      (libsource (lib "eagle-import") (part "CC1812GEN"))
    )
    (comp (ref "C118")
      (value "DNP")
      (footprint "eagle-import:C1812")
      (fields (field (name "PACKAGE") "1812") (field (name "BOM") "EXCLUDE") (field (name "VOLTAGE") "250V"))
      (libsource (lib "eagle-import") (part "CC1812GEN"))
    )
    (comp (ref "L101")
      (value "47nH")
      (footprint "eagle-import:L1008")
      (fields (field (name "PARTNO") "1008CS-470XJLC"))
      (libsource (lib "eagle-import") (part "L_CHIP1008L-47N-AIR-5%-1008-1A"))
    )
    (comp (ref "L102")
      (value "47nH")
      (footprint "eagle-import:L1008")
      (fields (field (name "PARTNO") "1008CS-470XJLC"))
      (libsource (lib "eagle-import") (part "L_CHIP1008L-47N-AIR-5%-1008-1A"))
    )
    (comp (ref "L103")
      (value "3.3uH")
      (footprint "eagle-import:DR127")
      (fields (field (name "PARTNO") "DR127-3R3-R"))
      (libsource (lib "eagle-import") (part "LL-3.3U-FERRITE-20%-12.5X12.5MM-10.5A"))
    )
    (comp (ref "L104")
      (value "3.3uH")
      (footprint "eagle-import:DR127")
      (fields (field (name "PARTNO") "DR127-3R3-R"))
      (libsource (lib "eagle-import") (part "LL-3.3U-FERRITE-20%-12.5X12.5MM-10.5A"))
    )
    (comp (ref "Q101")
      (value "IRF520N")
      (footprint "eagle-import:TO220BV")
      (fields (field (name "PARTNO") "IRF630") (field (name "VOLTAGE") "200V"))
      (libsource (lib "eagle-import") (part "MOSFET_NTO-220-VERTIRF630"))
    )
    (comp (ref "Q102")
      (value "IRF630")
      (footprint "eagle-import:TO220BV")
      (fields (field (name "VOLTAGE") "200V"))
      (libsource (lib "eagle-import") (part "MOSFET_NTO-220-VERTIRF630"))
    )
    (comp (ref "R24")
      (value "0")
      (footprint "eagle-import:1206_IPC-7351B")
      (fields (field (name "BOM") "EXCLUDE"))
      (libsource (lib "eagle-import") (part "R901206_IPCGEN"))
    )
    (comp (ref "R53")
      (value "0")
      (footprint "eagle-import:1206_IPC-7351B")
      (fields (field (name "BOM") "EXCLUDE"))
      (libsource (lib "eagle-import") (part "R901206_IPCGEN"))
    )
    (comp (ref "R54")
      (value "0")
      (footprint "eagle-import:1206_IPC-7351B")
      (libsource (lib "eagle-import") (part "R901206_IPCGEN"))
    )
    (comp (ref "R101")
      (value "0")
      (footprint "eagle-import:0805_IPC-7351B")
      (libsource (lib "eagle-import") (part "R0805_IPCGEN"))
    )
    (comp (ref "R102")
      (value "75")
      (footprint "eagle-import:1206_IPC-7351B")
      (libsource (lib "eagle-import") (part "R1206_IPCGEN"))
    )
    (comp (ref "R103")
      (value "75")
      (footprint "eagle-import:1206_IPC-7351B")
      (libsource (lib "eagle-import") (part "R1206_IPCGEN"))
    )
    (comp (ref "R104")
      (value "4.99")
      (footprint "eagle-import:1206_IPC-7351B")
      (libsource (lib "eagle-import") (part "R901206_IPCGEN"))
    )
    (comp (ref "R105")
      (value "4.99")
      (footprint "eagle-import:1206_IPC-7351B")
      (libsource (lib "eagle-import") (part "R901206_IPCGEN"))
    )
    (comp (ref "R106")
      (value "75")
      (footprint "eagle-import:1206_IPC-7351B")
      (libsource (lib "eagle-import") (part "R1206_IPCGEN"))
    )
    (comp (ref "R107")
      (value "75")
      (footprint "eagle-import:1206_IPC-7351B")
      (libsource (lib "eagle-import") (part "R1206_IPCGEN"))
    )
    (comp (ref "R108")
      (value "100")
      (footprint "eagle-import:0805_IPC-7351B")
      (libsource (lib "eagle-import") (part "R0805_IPCGEN"))
    )
    (comp (ref "R109")
      (value "100")
      (footprint "eagle-import:1206_IPC-7351B")
      (libsource (lib "eagle-import") (part "R1206_IPCGEN"))
    )
    (comp (ref "R110")
      (value "100")
      (footprint "eagle-import:0805_IPC-7351B")
      (libsource (lib "eagle-import") (part "R0805_IPCGEN"))
    )
    (comp (ref "R111")
      (value "100")
      (footprint "eagle-import:1206_IPC-7351B")
      (libsource (lib "eagle-import") (part "R1206_IPCGEN"))
    )
    (comp (ref "R112")
      (value "DNP")
      (footprint "eagle-import:0805_IPC-7351B")
      (fields (field (name "BOM") "EXCLUDE"))
      (libsource (lib "eagle-import") (part "R0805_IPCGEN"))
    )
    (comp (ref "R113")
      (value "DNP")
      (footprint "eagle-import:0805_IPC-7351B")
      (fields (field (name "BOM") "EXCLUDE"))
      (libsource (lib "eagle-import") (part "R0805_IPCGEN"))
    )
    (comp (ref "R114")
      (value "15")
      (footprint "eagle-import:0805_IPC-7351B")
      (libsource (lib "eagle-import") (part "R900805_IPCGEN"))
    )
    (comp (ref "R115")
      (value "15")
      (footprint "eagle-import:0805_IPC-7351B")
      (libsource (lib "eagle-import") (part "R900805_IPCGEN"))
    )
    (comp (ref "R116")
      (value "DNP")
      (footprint "eagle-import:0805_IPC-7351B")
      (fields (field (name "BOM") "EXCLUDE"))
      (libsource (lib "eagle-import") (part "R0805_IPCGEN"))
    )
    (comp (ref "R117")
      (value "DNP")
      (footprint "eagle-import:0805_IPC-7351B")
      (fields (field (name "BOM") "EXCLUDE"))
      (libsource (lib "eagle-import") (part "R0805_IPCGEN"))
    )
    (comp (ref "R118")
      (value "330")
      (footprint "eagle-import:R2512")
      (libsource (lib "eagle-import") (part "R90R2512GEN"))
    )
    (comp (ref "R119")
      (value "270")
      (footprint "eagle-import:R2512")
      (libsource (lib "eagle-import") (part "R90R2512GEN"))
    )
    (comp (ref "R120")
      (value "330")
      (footprint "eagle-import:R2512")
      (libsource (lib "eagle-import") (part "R90R2512GEN"))
    )
    (comp (ref "R121")
      (value "270")
      (footprint "eagle-import:R2512")
      (libsource (lib "eagle-import") (part "R90R2512GEN"))
    )
    (comp (ref "R122")
      (value "2.7")
      (footprint "eagle-import:R2512")
      (libsource (lib "eagle-import") (part "RR2512GEN"))
    )
    (comp (ref "R123")
      (value "2.7")
      (footprint "eagle-import:R2512")
      (libsource (lib "eagle-import") (part "RR2512GEN"))
    )
    (comp (ref "R124")
      (value "2.7")
      (footprint "eagle-import:R2512")
      (libsource (lib "eagle-import") (part "RR2512GEN"))
    )
    (comp (ref "R125")
      (value "2.7")
      (footprint "eagle-import:R2512")
      (libsource (lib "eagle-import") (part "RR2512GEN"))
    )
    (comp (ref "R126")
      (value "2.7")
      (footprint "eagle-import:R2512")
      (libsource (lib "eagle-import") (part "RR2512GEN"))
    )
    (comp (ref "R127")
      (value "2.7")
      (footprint "eagle-import:R2512")
      (libsource (lib "eagle-import") (part "RR2512GEN"))
    )
    (comp (ref "R128")
      (value "3.3")
      (footprint "eagle-import:R2512")
      (libsource (lib "eagle-import") (part "RR2512GEN"))
    )
    (comp (ref "R129")
      (value "3.3")
      (footprint "eagle-import:R2512")
      (libsource (lib "eagle-import") (part "RR2512GEN"))
    )
    (comp (ref "R132")
      (value "0")
      (footprint "eagle-import:0805_IPC-7351B")
      (libsource (lib "eagle-import") (part "R0805_IPCGEN"))
    )
    (comp (ref "T1")
      (value "HP1_TRAFO")
      (footprint "eagle-import:HP1")
      (fields (field (name "PARTNO") "HP1-1400LB"))
      (libsource (lib "eagle-import") (part "HP1_TRAFO"))
    )
    (comp (ref "T102")
      (value "HP4_TRAFO")
      (footprint "eagle-import:HP4")
      (fields (field (name "PARTNO") "HP4-0140LB"))
      (libsource (lib "eagle-import") (part "HP4_TRAFO"))
    )
    (comp (ref "TP1")
      (value "PROBE_TPTP_5MM")
      (footprint "eagle-import:PROBE_TP_5MM")
      (libsource (lib "eagle-import") (part "PROBE_TPTP_5MM"))
    )
    (comp (ref "TP2")
      (value "PROBE_TPTP_7P5MM")
      (footprint "eagle-import:PROBE_TP_7P5MM")
      (libsource (lib "eagle-import") (part "PROBE_TPTP_7P5MM"))
    )
    (comp (ref "TP3")
      (value "PROBE_TPTP_5MM")
      (footprint "eagle-import:PROBE_TP_5MM")
      (libsource (lib "eagle-import") (part "PROBE_TPTP_5MM"))
    )
    (comp (ref "TP4")
      (value "PROBE_TPTP_7P5MM")
      (footprint "eagle-import:PROBE_TP_7P5MM")
      (libsource (lib "eagle-import") (part "PROBE_TPTP_7P5MM"))
    )
    (comp (ref "TP5")
      (value "PROBE_TPTP_7P5MM")
      (footprint "eagle-import:PROBE_TP_7P5MM")
      (libsource (lib "eagle-import") (part "PROBE_TPTP_7P5MM"))
    )
    (comp (ref "TP6")
      (value "PROBE_TPTP_7P5MM")
      (footprint "eagle-import:PROBE_TP_7P5MM")
      (libsource (lib "eagle-import") (part "PROBE_TPTP_7P5MM"))
    )
    (comp (ref "TP18")
      (value "PROBE_TPTP_5MM")
      (footprint "eagle-import:PROBE_TP_5MM")
      (libsource (lib "eagle-import") (part "PROBE_TPTP_5MM"))
    )
    (comp (ref "TP19")
      (value "PROBE_TPTP_5MM")
      (footprint "eagle-import:PROBE_TP_5MM")
      (libsource (lib "eagle-import") (part "PROBE_TPTP_5MM"))
    )
    (comp (ref "X4")
      (value "1-227161-0")
      (footprint "eagle-import:AMP_227161")
      (fields (field (name "MF") "TYCO ELECTRONICS") (field (name "MPN") "1-227161"))
      (libsource (lib "eagle-import") (part "?2271611--0"))
    )
    (comp (ref "C7")
      (value "2.2nF")
      (footprint "eagle-import:C1206")
      (fields (field (name "PACKAGE") "1206") (field (name "VOLTAGE") "100V"))
      (libsource (lib "eagle-import") (part "CC1206GEN"))
    )
    (comp (ref "C8")
      (value "22nF")
      (footprint "eagle-import:C1206")
      (fields
        (field (name "PARTNO") "C3216NP02E223J160AA")
        (field (name "VOLTAGE") "250V")
        (field (name "BOM") "EXCLUDE")
      )
      (libsource (lib "eagle-import") (part "CC1206C-22N-250V-5%-1206-NP0"))
    )
    (comp (ref "C9")
      (value "DNP")
      (footprint "eagle-import:0805_IPC-7351B")
      (fields (field (name "BOM") "EXCLUDE") (field (name "VOLTAGE") "50V"))
      (libsource (lib "eagle-import") (part "C0805_IPCGEN"))
    )
    (comp (ref "C10")
      (value "DNP")
      (footprint "eagle-import:0805_IPC-7351B")
      (fields (field (name "BOM") "EXCLUDE") (field (name "VOLTAGE") "50V"))
      (libsource (lib "eagle-import") (part "C0805_IPCGEN"))
    )
    (comp (ref "C11")
      (value "4.7nF")
      (footprint "eagle-import:0805_IPC-7351B")
      (fields (field (name "PACKAGE") "0805") (field (name "VOLTAGE") "50V"))
      (libsource (lib "eagle-import") (part "C0805_IPCGEN"))
    )
    (comp (ref "C12")
      (value "22nF")
      (footprint "eagle-import:0805_IPC-7351B")
      (fields (field (name "PACKAGE") "0805") (field (name "VOLTAGE") "50V"))
      (libsource (lib "eagle-import") (part "C0805_IPCGEN"))
    )
    (comp (ref "C16")
      (value "10pF")
      (footprint "eagle-import:0805_IPC-7351B")
      (fields (field (name "PACKAGE") "0805") (field (name "VOLTAGE") "50V"))
      (libsource (lib "eagle-import") (part "C0805_IPCGEN"))
    )
    (comp (ref "C17")
      (value "22nF")
      (footprint "eagle-import:0805_IPC-7351B")
      (fields (field (name "PACKAGE") "0805") (field (name "VOLTAGE") "50V"))
      (libsource (lib "eagle-import") (part "C0805_IPCGEN"))
    )
    (comp (ref "C18")
      (value "10pF")
      (footprint "eagle-import:0805_IPC-7351B")
      (fields (field (name "PACKAGE") "0805") (field (name "VOLTAGE") "50V"))
      (libsource (lib "eagle-import") (part "C0805_IPCGEN"))
    )
    (comp (ref "C19")
      (value "22nF")
      (footprint "eagle-import:0805_IPC-7351B")
      (fields (field (name "PACKAGE") "0805") (field (name "VOLTAGE") "50V"))
      (libsource (lib "eagle-import") (part "C0805_IPCGEN"))
    )
    (comp (ref "C20")
      (value "22nF")
      (footprint "eagle-import:0805_IPC-7351B")
      (fields (field (name "PACKAGE") "0805") (field (name "VOLTAGE") "50V"))
      (libsource (lib "eagle-import") (part "C0805_IPCGEN"))
    )
    (comp (ref "C22")
      (value "0.1uF")
      (footprint "eagle-import:0805_IPC-7351B")
      (fields (field (name "VOLTAGE") "25V"))
      (libsource (lib "eagle-import") (part "C0805_IPCGEN"))
    )
    (comp (ref "C26")
      (value "0.1uF")
      (footprint "eagle-import:0805_IPC-7351B")
      (fields (field (name "VOLTAGE") "25V"))
      (libsource (lib "eagle-import") (part "C0805_IPCGEN"))
    )
    (comp (ref "C27")
      (value "0.1uF")
      (footprint "eagle-import:0805_IPC-7351B")
      (fields (field (name "VOLTAGE") "25V"))
      (libsource (lib "eagle-import") (part "C0805_IPCGEN"))
    )
    (comp (ref "C29")
      (value "DNP")
      (footprint "eagle-import:C1812")
      (fields (field (name "BOM") "EXCLUDE") (field (name "VOLTAGE") "100V"))
      (libsource (lib "eagle-import") (part "CC1812GEN"))
    )
    (comp (ref "IC1")
      (value "LM741D")
      (footprint "eagle-import:SO08")
      (libsource (lib "eagle-import") (part "741DLM"))
    )
    (comp (ref "IC2")
      (value "LM741D")
      (footprint "eagle-import:SO08")
      (libsource (lib "eagle-import") (part "741DLM"))
    )
    (comp (ref "JP2")
      (value "PINHD-1X3")
      (footprint "eagle-import:1X03")
      (libsource (lib "eagle-import") (part "PINHD-1X3"))
    )
    (comp (ref "L1")
      (value "LDR74")
      (footprint "eagle-import:DR74")
      (libsource (lib "eagle-import") (part "LDR74"))
    )
    (comp (ref "L2")
      (value "47nH")
      (footprint "eagle-import:L1008")
      (fields (field (name "PARTNO") "1008CS-470XJLC"))
      (libsource (lib "eagle-import") (part "L_CHIP1008L-47N-AIR-5%-1008-1A"))
    )
    (comp (ref "Q1")
      (value "IRF630")
      (footprint "eagle-import:TO220BV")
      (fields (field (name "VOLTAGE") "200V"))
      (libsource (lib "eagle-import") (part "MOSFET_NTO-220-VERTIRF630"))
    )
    (comp (ref "R14")
      (value "1200")
      (footprint "eagle-import:R2512")
      (libsource (lib "eagle-import") (part "R90R2512GEN"))
    )
    (comp (ref "R15")
      (value "3")
      (footprint "eagle-import:R2512")
      (libsource (lib "eagle-import") (part "RR2512GEN"))
    )
    (comp (ref "R16")
      (value "3")
      (footprint "eagle-import:R2512")
      (libsource (lib "eagle-import") (part "RR2512GEN"))
    )
    (comp (ref "R17")
      (value "500")
      (footprint "eagle-import:1206_IPC-7351B")
      (libsource (lib "eagle-import") (part "R1206_IPCGEN"))
    )
    (comp (ref "R18")
      (value "DNP")
      (footprint "eagle-import:1206_IPC-7351B")
      (libsource (lib "eagle-import") (part "R1206_IPCGEN"))
    )
    (comp (ref "R19")
      (value "0")
      (footprint "eagle-import:1206_IPC-7351B")
      (libsource (lib "eagle-import") (part "R901206_IPCGEN"))
    )
    (comp (ref "R20")
      (value "300")
      (footprint "eagle-import:0805_IPC-7351B")
      (libsource (lib "eagle-import") (part "R900805_IPCGEN"))
    )
    (comp (ref "R21")
      (value "15")
      (footprint "eagle-import:0805_IPC-7351B")
      (libsource (lib "eagle-import") (part "R900805_IPCGEN"))
    )
    (comp (ref "R22")
      (value "DNP")
      (footprint "eagle-import:0805_IPC-7351B")
      (fields (field (name "BOM") "EXCLUDE"))
      (libsource (lib "eagle-import") (part "R0805_IPCGEN"))
    )
    (comp (ref "R23")
      (value "DNP")
      (footprint "eagle-import:0805_IPC-7351B")
      (fields (field (name "BOM") "EXCLUDE"))
      (libsource (lib "eagle-import") (part "R0805_IPCGEN"))
    )
    (comp (ref "R25")
      (value "100")
      (footprint "eagle-import:0805_IPC-7351B")
      (libsource (lib "eagle-import") (part "R0805_IPCGEN"))
    )
    (comp (ref "R26")
      (value "DNP")
      (footprint "eagle-import:1206_IPC-7351B")
      (libsource (lib "eagle-import") (part "R1206_IPCGEN"))
    )
    (comp (ref "R27")
      (value "300")
      (footprint "eagle-import:0805_IPC-7351B")
      (libsource (lib "eagle-import") (part "R900805_IPCGEN"))
    )
    (comp (ref "R28")
      (value "100")
      (footprint "eagle-import:0805_IPC-7351B")
      (libsource (lib "eagle-import") (part "R900805_IPCGEN"))
    )
    (comp (ref "R29")
      (value "50")
      (footprint "eagle-import:0805_IPC-7351B")
      (libsource (lib "eagle-import") (part "R900805_IPCGEN"))
    )
    (comp (ref "R30")
      (value "100")
      (footprint "eagle-import:0805_IPC-7351B")
      (libsource (lib "eagle-import") (part "R0805_IPCGEN"))
    )
    (comp (ref "R31")
      (value "100")
      (footprint "eagle-import:0805_IPC-7351B")
      (libsource (lib "eagle-import") (part "R900805_IPCGEN"))
    )
    (comp (ref "R32")
      (value "50")
      (footprint "eagle-import:0805_IPC-7351B")
      (libsource (lib "eagle-import") (part "R900805_IPCGEN"))
    )
    (comp (ref "R49")
      (value "10K")
      (footprint "eagle-import:0805_IPC-7351B")
      (libsource (lib "eagle-import") (part "R0805_IPCGEN"))
    )
    (comp (ref "R50")
      (value "10K")
      (footprint "eagle-import:0805_IPC-7351B")
      (libsource (lib "eagle-import") (part "R0805_IPCGEN"))
    )
    (comp (ref "TP20")
      (value "PROBE_TPTP_5MM")
      (footprint "eagle-import:PROBE_TP_5MM")
      (libsource (lib "eagle-import") (part "PROBE_TPTP_5MM"))
    )
    (comp (ref "TP21")
      (value "PROBE_TPTP_7P5MM")
      (footprint "eagle-import:PROBE_TP_7P5MM")
      (libsource (lib "eagle-import") (part "PROBE_TPTP_7P5MM"))
    )
    (comp (ref "TP27")
      (value "PROBE_TPTP_5MM")
      (footprint "eagle-import:PROBE_TP_5MM")
      (libsource (lib "eagle-import") (part "PROBE_TPTP_5MM"))
    )
    (comp (ref "X2")
      (value "1-227161-0")
      (footprint "eagle-import:AMP_227161")
      (fields (field (name "MF") "TYCO ELECTRONICS") (field (name "MPN") "1-227161"))
      (libsource (lib "eagle-import") (part "?2271611--0"))
    )
    (comp (ref "C30")
      (value "33pF")
      (footprint "eagle-import:0805_IPC-7351B")
      (fields (field (name "VOLTAGE") "50V"))
      (libsource (lib "eagle-import") (part "C0805_IPCGEN"))
    )
    (comp (ref "C31")
      (value "22uF")
      (footprint "eagle-import:E2,5-7")
      (fields (field (name "PARTNO") "860010773010") (field (name "VOLTAGE") "63V"))
      (libsource (lib "eagle-import") (part "CPOLE2,5-7C-22U-63V-20%-6.3DX12.5L-ELEC"))
    )
    (comp (ref "C401")
      (value "3300uF")
      (footprint "eagle-import:EB25D")
      (fields (field (name "PARTNO") "MAL225638332E3") (field (name "VOLTAGE") "63V"))
      (libsource (lib "eagle-import") (part "CPOLEB25DC-3300U-63V-20%-25DX37L-ELEC"))
    )
    (comp (ref "C402")
      (value "10uF")
      (footprint "eagle-import:C2220_CKG57N")
      (fields
        (field (name "BOM") "INCLUDE")
        (field (name "PACKAGE") "2220")
        (field (name "PARTNO") "CGA9N3X7S2A106M230KE")
        (field (name "VOLTAGE") "100V")
      )
      (libsource (lib "eagle-import") (part "CC2220_CKG57NCC-10U-100V-20%-2220-X7T"))
    )
    (comp (ref "C403")
      (value "6.8uF")
      (footprint "eagle-import:C1210")
      (fields (field (name "DIALECTRIC") "X7S") (field (name "VOLTAGE") "50V"))
      (libsource (lib "eagle-import") (part "CC1210GEN"))
    )
    (comp (ref "C404")
      (value "6.8uF")
      (footprint "eagle-import:C1210")
      (fields (field (name "DIALECTRIC") "X7S") (field (name "VOLTAGE") "50V"))
      (libsource (lib "eagle-import") (part "CC1210GEN"))
    )
    (comp (ref "C405")
      (value "10uF")
      (footprint "eagle-import:C2220_CKG57N")
      (fields
        (field (name "BOM") "INCLUDE")
        (field (name "PACKAGE") "2220")
        (field (name "PARTNO") "CGA9N3X7S2A106M230KE")
        (field (name "VOLTAGE") "100V")
      )
      (libsource (lib "eagle-import") (part "CC2220_CKG57NCC-10U-100V-20%-2220-X7T"))
    )
    (comp (ref "C406")
      (value "4.7uF")
      (footprint "eagle-import:C1206")
      (fields (field (name "DIALECTRIC") "X7R") (field (name "VOLTAGE") "50V"))
      (libsource (lib "eagle-import") (part "CC1206GEN"))
    )
    (comp (ref "C407")
      (value "4.7uF")
      (footprint "eagle-import:C1206")
      (fields (field (name "DIALECTRIC") "X7R") (field (name "VOLTAGE") "50V"))
      (libsource (lib "eagle-import") (part "CC1206GEN"))
    )
    (comp (ref "C408")
      (value "10uF")
      (footprint "eagle-import:C2220_CKG57N")
      (fields (field (name "PARTNO") "CGA9N3X7S2A106M230KE") (field (name "VOLTAGE") "100V"))
      (libsource (lib "eagle-import") (part "CC2220_CKG57NCC-10U-100V-20%-2220-X7T"))
    )
    (comp (ref "C409")
      (value "22uF")
      (footprint "eagle-import:E2,5-7")
      (fields (field (name "PARTNO") "860010773010") (field (name "VOLTAGE") "63V"))
      (libsource (lib "eagle-import") (part "CPOLE2,5-7C-22U-63V-20%-6.3DX12.5L-ELEC"))
    )
    (comp (ref "C410")
      (value "22uF")
      (footprint "eagle-import:E2,5-7")
      (fields (field (name "PARTNO") "860010773010") (field (name "VOLTAGE") "63V"))
      (libsource (lib "eagle-import") (part "CPOLE2,5-7C-22U-63V-20%-6.3DX12.5L-ELEC"))
    )
    (comp (ref "C411")
      (value "10uF")
      (footprint "eagle-import:C2220_CKG57N")
      (fields (field (name "PARTNO") "CGA9N3X7S2A106M230KE") (field (name "VOLTAGE") "100V"))
      (libsource (lib "eagle-import") (part "CC2220_CKG57NCC-10U-100V-20%-2220-X7T"))
    )
    (comp (ref "C412")
      (value "10uF")
      (footprint "eagle-import:C2220_CKG57N")
      (fields (field (name "PARTNO") "CGA9N3X7S2A106M230KE") (field (name "VOLTAGE") "100V"))
      (libsource (lib "eagle-import") (part "CC2220_CKG57NCC-10U-100V-20%-2220-X7T"))
    )
    (comp (ref "C413")
      (value "10uF")
      (footprint "eagle-import:C2220_CKG57N")
      (fields (field (name "PARTNO") "CGA9N3X7S2A106M230KE") (field (name "VOLTAGE") "100V"))
      (libsource (lib "eagle-import") (part "CC2220_CKG57NCC-10U-100V-20%-2220-X7T"))
    )
    (comp (ref "D401")
      (value "D-SCHOTTKYSK810L-TPSMC")
      (footprint "eagle-import:DO-214AB(SMC)")
      (fields (field (name "PARTNO") "SK810L-TP") (field (name "VOLTAGE") "100V"))
      (libsource (lib "eagle-import") (part "D-SCHOTTKYSMCSK810L-TP"))
    )
    (comp (ref "F401")
      (value "FUSE_2P")
      (footprint "eagle-import:02540121Z")
      (fields (field (name "PARTNO") "02540121Z"))
      (libsource (lib "eagle-import") (part "FUSE_2P"))
    )
    (comp (ref "H1")
      (value "MOUNT-PAD-SQUARE3.2")
      (footprint "eagle-import:3,2-PAD-SQUARE")
      (libsource (lib "eagle-import") (part "MOUNT-PAD-SQUARE3.2"))
    )
    (comp (ref "H2")
      (value "MOUNT-PAD-SQUARE3.2")
      (footprint "eagle-import:3,2-PAD-SQUARE")
      (libsource (lib "eagle-import") (part "MOUNT-PAD-SQUARE3.2"))
    )
    (comp (ref "H401")
      (value "MOUNT-PAD-SQUARE3.2")
      (footprint "eagle-import:3,2-PAD-SQUARE")
      (libsource (lib "eagle-import") (part "MOUNT-PAD-SQUARE3.2"))
    )
    (comp (ref "H402")
      (value "MOUNT-PAD-SQUARE3.2")
      (footprint "eagle-import:3,2-PAD-SQUARE")
      (libsource (lib "eagle-import") (part "MOUNT-PAD-SQUARE3.2"))
    )
    (comp (ref "H403")
      (value "MOUNT-PAD-SQUARE3.2")
      (footprint "eagle-import:3,2-PAD-SQUARE")
      (libsource (lib "eagle-import") (part "MOUNT-PAD-SQUARE3.2"))
    )
    (comp (ref "H404")
      (value "MOUNT-PAD-SQUARE3.2")
      (footprint "eagle-import:3,2-PAD-SQUARE")
      (libsource (lib "eagle-import") (part "MOUNT-PAD-SQUARE3.2"))
    )
    (comp (ref "J401")
      (value "HDR_2X1282836-1282836-1")
      (footprint "eagle-import:W237-02")
      (fields (field (name "PARTNO") "282836-1"))
      (libsource (lib "eagle-import") (part "HDR_2X1282836-1282836-1"))
    )
    (comp (ref "J402")
      (value "KK_PCFAN")
      (footprint "eagle-import:47053-1000")
      (fields (field (name "PARTNO") "47053-1000"))
      (libsource (lib "eagle-import") (part "KK_PCFAN"))
    )
    (comp (ref "L401")
      (value "3.3uH")
      (footprint "eagle-import:DR127")
      (fields (field (name "PARTNO") "DR127-3R3-R"))
      (libsource (lib "eagle-import") (part "LL-3.3U-FERRITE-20%-12.5X12.5MM-10.5A"))
    )
    (comp (ref "L402")
      (value "22uH")
      (footprint "eagle-import:DR127")
      (fields (field (name "PARTNO") "DR127-220-R"))
      (libsource (lib "eagle-import") (part "LL-22U-FERRITE-20%-12.5X12.5MM-4A"))
    )
    (comp (ref "LED402")
      (value "LEDT1_3/4_RA")
      (footprint "eagle-import:LED_5MM_RA")
      (libsource (lib "eagle-import") (part "LEDT1_3/4_RA"))
    )
    (comp (ref "Q6")
      (value "NPN_DARGLINGTONTIP122TO220BV")
      (footprint "eagle-import:TO220BV")
      (fields (field (name "PARTNO") "TIP122G") (field (name "VOLTAGE") "100V"))
      (libsource (lib "eagle-import") (part "NPN_DARGLINGTONTO220BVTIP122"))
    )
    (comp (ref "R55")
      (value "590")
      (footprint "eagle-import:0805_IPC-7351B")
      (libsource (lib "eagle-import") (part "R0805_IPCGEN"))
    )
    (comp (ref "R56")
      (value "590")
      (footprint "eagle-import:0805_IPC-7351B")
      (libsource (lib "eagle-import") (part "R0805_IPCGEN"))
    )
    (comp (ref "R57")
      (value "590")
      (footprint "eagle-import:0805_IPC-7351B")
      (libsource (lib "eagle-import") (part "R0805_IPCGEN"))
    )
    (comp (ref "R401")
      (value "1.0")
      (footprint "eagle-import:P0817V")
      (fields (field (name "PARTNO") "PAC300001008FAC000") (field (name "POWER") "3W"))
      (libsource (lib "eagle-import") (part "R90P0817VR-1.0-1%-AXIAL-3W"))
    )
    (comp (ref "R404")
      (value "1.0")
      (footprint "eagle-import:1206_IPC-7351B")
      (libsource (lib "eagle-import") (part "R901206_IPCGEN"))
    )
    (comp (ref "R405")
      (value "0.5")
      (footprint "eagle-import:1206_IPC-7351B")
      (libsource (lib "eagle-import") (part "R901206_IPCGEN"))
    )
    (comp (ref "R407")
      (value "590")
      (footprint "eagle-import:0805_IPC-7351B")
      (libsource (lib "eagle-import") (part "R0805_IPCGEN"))
    )
    (comp (ref "R408")
      (value "10K")
      (footprint "eagle-import:0805_IPC-7351B")
      (libsource (lib "eagle-import") (part "R900805_IPCGEN"))
    )
    (comp (ref "U2")
      (value "ADJ_ZENERTL431AILPRAGTO-92-LPRE")
      (footprint "eagle-import:TO-92-FORMED")
      (fields (field (name "PARTNO") "TL431AILPRAG") (field (name "VOLTAGE") "2.5-36V"))
      (libsource (lib "eagle-import") (part "ADJ_ZENERTO-92-LPRETL431AILPRAG"))
    )
    (comp (ref "U401")
      (value "LDO_3TERMMC78M12CTGTO220_VERT")
      (footprint "eagle-import:TO220BV")
      (fields (field (name "PARTNO") "MC78M12CTG"))
      (libsource (lib "eagle-import") (part "LDO_3TERMTO220_VERTMC78M12CTG"))
    )
    (comp (ref "U402")
      (value "LDO_3TERMMC78M05CTGTO220_VERT")
      (footprint "eagle-import:TO220BV")
      (fields (field (name "PARTNO") "MC78M05CTG"))
      (libsource (lib "eagle-import") (part "LDO_3TERMTO220_VERTMC78M05CTG"))
    )
    (comp (ref "X6")
      (value "HEATSINK_CLIPONATS-PCBT1085ATS-PCBT1085")
      (footprint "eagle-import:ATS-PCBT1085")
      (fields (field (name "PARTNO") "ATS-PCBT1085"))
      (libsource (lib "eagle-import") (part "HEATSINK_CLIPONATS-PCBT1085ATS-PCBT1085"))
    )
    (comp (ref "X7")
      (value "HEATSINK_CLIPONATS-PCBT1085ATS-PCBT1085")
      (footprint "eagle-import:ATS-PCBT1085")
      (fields (field (name "PARTNO") "ATS-PCBT1085"))
      (libsource (lib "eagle-import") (part "HEATSINK_CLIPONATS-PCBT1085ATS-PCBT1085"))
    )
    (comp (ref "X402")
      (value "HEATSINK_OMNI_DUALOMNI-UNI-30-75-D30-75-D")
      (footprint "eagle-import:OMNI-UNI-30-75-D")
      (fields (field (name "PARTNO") "OMNI-UNI-30-75-D"))
      (libsource (lib "eagle-import") (part "HEATSINK_OMNI_DUAL30-75-DOMNI-UNI-30-75-D"))
    )
    (comp (ref "C201")
      (value "22nF")
      (footprint "eagle-import:0805_IPC-7351B")
      (fields (field (name "PACKAGE") "0805") (field (name "VOLTAGE") "50V"))
      (libsource (lib "eagle-import") (part "C0805_IPCGEN"))
    )
    (comp (ref "C202")
      (value "27nF")
      (footprint "eagle-import:0805_IPC-7351B")
      (fields (field (name "PACKAGE") "0805") (field (name "VOLTAGE") "50V"))
      (libsource (lib "eagle-import") (part "C0805_IPCGEN"))
    )
    (comp (ref "C203")
      (value "22nF")
      (footprint "eagle-import:0805_IPC-7351B")
      (fields (field (name "PACKAGE") "0805") (field (name "VOLTAGE") "50V"))
      (libsource (lib "eagle-import") (part "C0805_IPCGEN"))
    )
    (comp (ref "C204")
      (value "27nF")
      (footprint "eagle-import:0805_IPC-7351B")
      (fields (field (name "PACKAGE") "0805") (field (name "VOLTAGE") "50V"))
      (libsource (lib "eagle-import") (part "C0805_IPCGEN"))
    )
    (comp (ref "C205")
      (value "DNP")
      (footprint "eagle-import:0805_IPC-7351B")
      (fields (field (name "BOM") "EXCLUDE") (field (name "VOLTAGE") "50V"))
      (libsource (lib "eagle-import") (part "C0805_IPCGEN"))
    )
    (comp (ref "C206")
      (value "DNP")
      (footprint "eagle-import:0805_IPC-7351B")
      (fields (field (name "BOM") "EXCLUDE") (field (name "VOLTAGE") "50V"))
      (libsource (lib "eagle-import") (part "C0805_IPCGEN"))
    )
    (comp (ref "C207")
      (value "DNP")
      (footprint "eagle-import:0805_IPC-7351B")
      (fields (field (name "BOM") "EXCLUDE") (field (name "VOLTAGE") "50V"))
      (libsource (lib "eagle-import") (part "C0805_IPCGEN"))
    )
    (comp (ref "C208")
      (value "DNP")
      (footprint "eagle-import:0805_IPC-7351B")
      (fields (field (name "BOM") "EXCLUDE") (field (name "VOLTAGE") "50V"))
      (libsource (lib "eagle-import") (part "C0805_IPCGEN"))
    )
    (comp (ref "C209")
      (value "2.2nF")
      (footprint "eagle-import:C1206")
      (fields (field (name "PACKAGE") "1206") (field (name "VOLTAGE") "100V"))
      (libsource (lib "eagle-import") (part "CC1206GEN"))
    )
    (comp (ref "C210")
      (value "2.2nF")
      (footprint "eagle-import:C1206")
      (fields (field (name "PACKAGE") "1206") (field (name "VOLTAGE") "100V"))
      (libsource (lib "eagle-import") (part "CC1206GEN"))
    )
    (comp (ref "L201")
      (value "47nH")
      (footprint "eagle-import:L1008")
      (fields (field (name "PARTNO") "1008CS-470XJLC"))
      (libsource (lib "eagle-import") (part "L_CHIP1008L-47N-AIR-5%-1008-1A"))
    )
    (comp (ref "L202")
      (value "47nH")
      (footprint "eagle-import:L1008")
      (fields (field (name "PARTNO") "1008CS-470XJLC"))
      (libsource (lib "eagle-import") (part "L_CHIP1008L-47N-AIR-5%-1008-1A"))
    )
    (comp (ref "Q201")
      (value "IRF630")
      (footprint "eagle-import:TO220BV")
      (fields (field (name "VOLTAGE") "200V"))
      (libsource (lib "eagle-import") (part "MOSFET_NTO-220-VERTIRF630"))
    )
    (comp (ref "Q202")
      (value "IRF630")
      (footprint "eagle-import:TO220BV")
      (fields (field (name "VOLTAGE") "200V"))
      (libsource (lib "eagle-import") (part "MOSFET_NTO-220-VERTIRF630"))
    )
    (comp (ref "R201")
      (value "75")
      (footprint "eagle-import:1206_IPC-7351B")
      (libsource (lib "eagle-import") (part "R1206_IPCGEN"))
    )
    (comp (ref "R202")
      (value "75")
      (footprint "eagle-import:1206_IPC-7351B")
      (libsource (lib "eagle-import") (part "R1206_IPCGEN"))
    )
    (comp (ref "R203")
      (value "4.99")
      (footprint "eagle-import:1206_IPC-7351B")
      (libsource (lib "eagle-import") (part "R901206_IPCGEN"))
    )
    (comp (ref "R204")
      (value "4.99")
      (footprint "eagle-import:1206_IPC-7351B")
      (libsource (lib "eagle-import") (part "R901206_IPCGEN"))
    )
    (comp (ref "R205")
      (value "75")
      (footprint "eagle-import:1206_IPC-7351B")
      (libsource (lib "eagle-import") (part "R1206_IPCGEN"))
    )
    (comp (ref "R206")
      (value "75")
      (footprint "eagle-import:1206_IPC-7351B")
      (libsource (lib "eagle-import") (part "R1206_IPCGEN"))
    )
    (comp (ref "R207")
      (value "100")
      (footprint "eagle-import:0805_IPC-7351B")
      (libsource (lib "eagle-import") (part "R0805_IPCGEN"))
    )
    (comp (ref "R208")
      (value "100")
      (footprint "eagle-import:1206_IPC-7351B")
      (libsource (lib "eagle-import") (part "R1206_IPCGEN"))
    )
    (comp (ref "R209")
      (value "100")
      (footprint "eagle-import:0805_IPC-7351B")
      (libsource (lib "eagle-import") (part "R0805_IPCGEN"))
    )
    (comp (ref "R210")
      (value "100")
      (footprint "eagle-import:1206_IPC-7351B")
      (libsource (lib "eagle-import") (part "R1206_IPCGEN"))
    )
    (comp (ref "R211")
      (value "DNP")
      (footprint "eagle-import:0805_IPC-7351B")
      (fields (field (name "BOM") "EXCLUDE"))
      (libsource (lib "eagle-import") (part "R0805_IPCGEN"))
    )
    (comp (ref "R212")
      (value "DNP")
      (footprint "eagle-import:0805_IPC-7351B")
      (fields (field (name "BOM") "EXCLUDE"))
      (libsource (lib "eagle-import") (part "R0805_IPCGEN"))
    )
    (comp (ref "R213")
      (value "15")
      (footprint "eagle-import:0805_IPC-7351B")
      (libsource (lib "eagle-import") (part "R900805_IPCGEN"))
    )
    (comp (ref "R214")
      (value "15")
      (footprint "eagle-import:0805_IPC-7351B")
      (libsource (lib "eagle-import") (part "R900805_IPCGEN"))
    )
    (comp (ref "R215")
      (value "DNP")
      (footprint "eagle-import:0805_IPC-7351B")
      (fields (field (name "BOM") "EXCLUDE"))
      (libsource (lib "eagle-import") (part "R0805_IPCGEN"))
    )
    (comp (ref "R216")
      (value "DNP")
      (footprint "eagle-import:0805_IPC-7351B")
      (fields (field (name "BOM") "EXCLUDE"))
      (libsource (lib "eagle-import") (part "R0805_IPCGEN"))
    )
    (comp (ref "R217")
      (value "330")
      (footprint "eagle-import:R2512")
      (libsource (lib "eagle-import") (part "R90R2512GEN"))
    )
    (comp (ref "R218")
      (value "270")
      (footprint "eagle-import:R2512")
      (libsource (lib "eagle-import") (part "R90R2512GEN"))
    )
    (comp (ref "R219")
      (value "330")
      (footprint "eagle-import:R2512")
      (libsource (lib "eagle-import") (part "R90R2512GEN"))
    )
    (comp (ref "R220")
      (value "270")
      (footprint "eagle-import:R2512")
      (libsource (lib "eagle-import") (part "R90R2512GEN"))
    )
    (comp (ref "R221")
      (value "2.7")
      (footprint "eagle-import:R2512")
      (libsource (lib "eagle-import") (part "RR2512GEN"))
    )
    (comp (ref "R222")
      (value "2.7")
      (footprint "eagle-import:R2512")
      (libsource (lib "eagle-import") (part "RR2512GEN"))
    )
    (comp (ref "R223")
      (value "2.7")
      (footprint "eagle-import:R2512")
      (libsource (lib "eagle-import") (part "RR2512GEN"))
    )
    (comp (ref "R224")
      (value "2.7")
      (footprint "eagle-import:R2512")
      (libsource (lib "eagle-import") (part "RR2512GEN"))
    )
    (comp (ref "R225")
      (value "2.7")
      (footprint "eagle-import:R2512")
      (libsource (lib "eagle-import") (part "RR2512GEN"))
    )
    (comp (ref "R226")
      (value "2.7")
      (footprint "eagle-import:R2512")
      (libsource (lib "eagle-import") (part "RR2512GEN"))
    )
    (comp (ref "R227")
      (value "3.3")
      (footprint "eagle-import:R2512")
      (libsource (lib "eagle-import") (part "RR2512GEN"))
    )
    (comp (ref "R228")
      (value "3.3")
      (footprint "eagle-import:R2512")
      (libsource (lib "eagle-import") (part "RR2512GEN"))
    )
    (comp (ref "TP7")
      (value "PROBE_TPTP_5MM")
      (footprint "eagle-import:PROBE_TP_5MM")
      (libsource (lib "eagle-import") (part "PROBE_TPTP_5MM"))
    )
    (comp (ref "TP8")
      (value "PROBE_TPTP_7P5MM")
      (footprint "eagle-import:PROBE_TP_7P5MM")
      (libsource (lib "eagle-import") (part "PROBE_TPTP_7P5MM"))
    )
    (comp (ref "TP9")
      (value "PROBE_TPTP_5MM")
      (footprint "eagle-import:PROBE_TP_5MM")
      (libsource (lib "eagle-import") (part "PROBE_TPTP_5MM"))
    )
    (comp (ref "TP10")
      (value "PROBE_TPTP_7P5MM")
      (footprint "eagle-import:PROBE_TP_7P5MM")
      (libsource (lib "eagle-import") (part "PROBE_TPTP_7P5MM"))
    )
  )
  (nets
    (net (code "1") (name "+5V") (class "Default")
      (node (ref "C23") (pin "1") (pinfunction "1_1") (pintype "passive"))
      (node (ref "C24") (pin "1") (pinfunction "1_1") (pintype "passive"))
      (node (ref "C25") (pin "1") (pinfunction "1_1") (pintype "passive"))
      (node (ref "C28") (pin "1") (pinfunction "1_1") (pintype "passive"))
      (node (ref "C407") (pin "1") (pinfunction "1_1") (pintype "passive"))
      (node (ref "C410") (pin "+") (pinfunction "+_+") (pintype "passive"))
      (node (ref "D3") (pin "K") (pinfunction "C1_K") (pintype "passive"))
      (node (ref "IC3") (pin "8") (pinfunction "V+_8") (pintype "power_in"))
      (node (ref "IC5") (pin "5") (pinfunction "VCC_5") (pintype "power_in"))
      (node (ref "IC6") (pin "10") (pinfunction "PRE_10") (pintype "input"))
      (node (ref "IC6") (pin "14") (pinfunction "VCC_14") (pintype "power_in"))
      (node (ref "IC6") (pin "2") (pinfunction "D_2") (pintype "input"))
      (node (ref "IC7") (pin "5") (pinfunction "VCC_5") (pintype "power_in"))
      (node (ref "JP1") (pin "2") (pinfunction "2_2") (pintype "passive"))
      (node (ref "LED1") (pin "A") (pinfunction "A_A") (pintype "passive"))
      (node (ref "R10") (pin "1") (pinfunction "1_1") (pintype "passive"))
      (node (ref "R13") (pin "3") (pinfunction "E_3") (pintype "passive"))
      (node (ref "R301") (pin "3") (pinfunction "E_3") (pintype "passive"))
      (node (ref "R33") (pin "3") (pinfunction "E_3") (pintype "passive"))
      (node (ref "R34") (pin "3") (pinfunction "E_3") (pintype "passive"))
      (node (ref "R407") (pin "1") (pinfunction "1_1") (pintype "passive"))
      (node (ref "R408") (pin "1") (pinfunction "1_1") (pintype "passive"))
      (node (ref "R9") (pin "1") (pinfunction "1_1") (pintype "passive"))
      (node (ref "SW2") (pin "2") (pinfunction "P1_2") (pintype "passive"))
      (node (ref "U402") (pin "3") (pinfunction "OUT_3") (pintype "passive"))
    )
    (net (code "2") (name "+24V") (class "Default")
      (node (ref "C22") (pin "1") (pinfunction "1_1") (pintype "passive"))
      (node (ref "C26") (pin "1") (pinfunction "1_1") (pintype "passive"))
      (node (ref "C31") (pin "+") (pinfunction "+_+") (pintype "passive"))
      (node (ref "C403") (pin "1") (pinfunction "1_1") (pintype "passive"))
      (node (ref "C404") (pin "1") (pinfunction "1_1") (pintype "passive"))
      (node (ref "IC1") (pin "7") (pinfunction "V+_7") (pintype "power_in"))
      (node (ref "IC2") (pin "7") (pinfunction "V+_7") (pintype "power_in"))
      (node (ref "Q6") (pin "S") (pinfunction "E_S") (pintype "passive"))
      (node (ref "R49") (pin "1") (pinfunction "1_1") (pintype "passive"))
      (node (ref "R57") (pin "1") (pinfunction "1_1") (pintype "passive"))
      (node (ref "U401") (pin "1") (pinfunction "IN_1") (pintype "input"))
      (node (ref "U402") (pin "1") (pinfunction "IN_1") (pintype "input"))
    )
    (net (code "3") (name "ABN1") (class "Default")
      (node (ref "R103") (pin "1") (pinfunction "1_1") (pintype "passive"))
      (node (ref "R105") (pin "1") (pinfunction "1_1") (pintype "passive"))
      (node (ref "R202") (pin "1") (pinfunction "1_1") (pintype "passive"))
      (node (ref "R204") (pin "1") (pinfunction "1_1") (pintype "passive"))
      (node (ref "T1") (pin "11") (pinfunction "F2_11") (pintype "passive"))
      (node (ref "TP18") (pin "TP") (pinfunction "1_TP") (pintype "passive"))
    )
    (net (code "4") (name "ABP1") (class "Default")
      (node (ref "R102") (pin "1") (pinfunction "1_1") (pintype "passive"))
      (node (ref "R104") (pin "1") (pinfunction "1_1") (pintype "passive"))
      (node (ref "R201") (pin "1") (pinfunction "1_1") (pintype "passive"))
      (node (ref "R203") (pin "1") (pinfunction "1_1") (pintype "passive"))
      (node (ref "T1") (pin "1") (pinfunction "S1_1") (pintype "passive"))
      (node (ref "TP19") (pin "TP") (pinfunction "1_TP") (pintype "passive"))
    )
    (net (code "5") (name "AN2") (class "Default")
      (node (ref "C107") (pin "2") (pinfunction "2_2") (pintype "passive"))
      (node (ref "R105") (pin "2") (pinfunction "2_2") (pintype "passive"))
      (node (ref "R107") (pin "1") (pinfunction "1_1") (pintype "passive"))
    )
    (net (code "6") (name "AN3") (class "Default")
      (node (ref "C107") (pin "1") (pinfunction "1_1") (pintype "passive"))
      (node (ref "L102") (pin "1") (pinfunction "1_1") (pintype "passive"))
      (node (ref "R111") (pin "2") (pinfunction "2_2") (pintype "passive"))
      (node (ref "R113") (pin "1") (pinfunction "1_1") (pintype "passive"))
      (node (ref "R115") (pin "1") (pinfunction "1_1") (pintype "passive"))
    )
    (net (code "7") (name "AN4") (class "Default")
      (node (ref "L102") (pin "2") (pinfunction "2_2") (pintype "passive"))
      (node (ref "Q102") (pin "G") (pinfunction "G_G") (pintype "passive"))
      (node (ref "R115") (pin "2") (pinfunction "2_2") (pintype "passive"))
      (node (ref "R117") (pin "1") (pinfunction "1_1") (pintype "passive"))
      (node (ref "R120") (pin "1") (pinfunction "1_1") (pintype "passive"))
      (node (ref "R121") (pin "1") (pinfunction "1_1") (pintype "passive"))
      (node (ref "TP3") (pin "TP") (pinfunction "1_TP") (pintype "passive"))
    )
    (net (code "8") (name "AN5") (class "Default")
      (node (ref "Q102") (pin "S") (pinfunction "S_S") (pintype "passive"))
      (node (ref "R123") (pin "1") (pinfunction "1_1") (pintype "passive"))
      (node (ref "R125") (pin "1") (pinfunction "1_1") (pintype "passive"))
      (node (ref "R127") (pin "1") (pinfunction "1_1") (pintype "passive"))
      (node (ref "R129") (pin "1") (pinfunction "1_1") (pintype "passive"))
      (node (ref "R45") (pin "2") (pinfunction "2_2") (pintype "passive"))
      (node (ref "TP6") (pin "TP") (pinfunction "1_TP") (pintype "passive"))
    )
    (net (code "9") (name "AP2") (class "Default")
      (node (ref "C105") (pin "2") (pinfunction "2_2") (pintype "passive"))
      (node (ref "R104") (pin "2") (pinfunction "2_2") (pintype "passive"))
      (node (ref "R106") (pin "1") (pinfunction "1_1") (pintype "passive"))
    )
    (net (code "10") (name "AP3") (class "Default")
      (node (ref "C105") (pin "1") (pinfunction "1_1") (pintype "passive"))
      (node (ref "L101") (pin "1") (pinfunction "1_1") (pintype "passive"))
      (node (ref "R109") (pin "2") (pinfunction "2_2") (pintype "passive"))
      (node (ref "R112") (pin "1") (pinfunction "1_1") (pintype "passive"))
      (node (ref "R114") (pin "1") (pinfunction "1_1") (pintype "passive"))
    )
    (net (code "11") (name "AP4") (class "Default")
      (node (ref "L101") (pin "2") (pinfunction "2_2") (pintype "passive"))
      (node (ref "Q101") (pin "G") (pinfunction "G_G") (pintype "passive"))
      (node (ref "R114") (pin "2") (pinfunction "2_2") (pintype "passive"))
      (node (ref "R116") (pin "1") (pinfunction "1_1") (pintype "passive"))
      (node (ref "R118") (pin "1") (pinfunction "1_1") (pintype "passive"))
      (node (ref "R119") (pin "1") (pinfunction "1_1") (pintype "passive"))
      (node (ref "TP1") (pin "TP") (pinfunction "1_TP") (pintype "passive"))
    )
    (net (code "12") (name "AP5") (class "Default")
      (node (ref "Q101") (pin "S") (pinfunction "S_S") (pintype "passive"))
      (node (ref "R122") (pin "1") (pinfunction "1_1") (pintype "passive"))
      (node (ref "R124") (pin "1") (pinfunction "1_1") (pintype "passive"))
      (node (ref "R126") (pin "1") (pinfunction "1_1") (pintype "passive"))
      (node (ref "R128") (pin "1") (pinfunction "1_1") (pintype "passive"))
      (node (ref "R44") (pin "2") (pinfunction "2_2") (pintype "passive"))
      (node (ref "TP5") (pin "TP") (pinfunction "1_TP") (pintype "passive"))
    )
    (net (code "13") (name "BLANK_POL") (class "Default")
      (node (ref "IC7") (pin "2") (pinfunction "I1_2") (pintype "input"))
      (node (ref "JP1") (pin "1") (pinfunction "1_1") (pintype "passive"))
      (node (ref "R11") (pin "1") (pinfunction "1_1") (pintype "passive"))
      (node (ref "R307") (pin "2") (pinfunction "2_2") (pintype "passive"))
    )
    (net (code "14") (name "BN2") (class "Default")
      (node (ref "C204") (pin "2") (pinfunction "2_2") (pintype "passive"))
      (node (ref "R204") (pin "2") (pinfunction "2_2") (pintype "passive"))
      (node (ref "R206") (pin "1") (pinfunction "1_1") (pintype "passive"))
    )
    (net (code "15") (name "BN3") (class "Default")
      (node (ref "C204") (pin "1") (pinfunction "1_1") (pintype "passive"))
      (node (ref "L202") (pin "1") (pinfunction "1_1") (pintype "passive"))
      (node (ref "R210") (pin "2") (pinfunction "2_2") (pintype "passive"))
      (node (ref "R212") (pin "1") (pinfunction "1_1") (pintype "passive"))
      (node (ref "R214") (pin "1") (pinfunction "1_1") (pintype "passive"))
    )
    (net (code "16") (name "BN4") (class "Default")
      (node (ref "L202") (pin "2") (pinfunction "2_2") (pintype "passive"))
      (node (ref "Q202") (pin "G") (pinfunction "G_G") (pintype "passive"))
      (node (ref "R214") (pin "2") (pinfunction "2_2") (pintype "passive"))
      (node (ref "R216") (pin "1") (pinfunction "1_1") (pintype "passive"))
      (node (ref "R219") (pin "1") (pinfunction "1_1") (pintype "passive"))
      (node (ref "R220") (pin "1") (pinfunction "1_1") (pintype "passive"))
      (node (ref "TP9") (pin "TP") (pinfunction "1_TP") (pintype "passive"))
    )
    (net (code "17") (name "BN5") (class "Default")
      (node (ref "Q202") (pin "S") (pinfunction "S_S") (pintype "passive"))
      (node (ref "R222") (pin "1") (pinfunction "1_1") (pintype "passive"))
      (node (ref "R224") (pin "1") (pinfunction "1_1") (pintype "passive"))
      (node (ref "R226") (pin "1") (pinfunction "1_1") (pintype "passive"))
      (node (ref "R228") (pin "1") (pinfunction "1_1") (pintype "passive"))
      (node (ref "R47") (pin "2") (pinfunction "2_2") (pintype "passive"))
      (node (ref "TP10") (pin "TP") (pinfunction "1_TP") (pintype "passive"))
    )
    (net (code "18") (name "BP2") (class "Default")
      (node (ref "C202") (pin "2") (pinfunction "2_2") (pintype "passive"))
      (node (ref "R203") (pin "2") (pinfunction "2_2") (pintype "passive"))
      (node (ref "R205") (pin "1") (pinfunction "1_1") (pintype "passive"))
    )
    (net (code "19") (name "BP3") (class "Default")
      (node (ref "C202") (pin "1") (pinfunction "1_1") (pintype "passive"))
      (node (ref "L201") (pin "1") (pinfunction "1_1") (pintype "passive"))
      (node (ref "R208") (pin "2") (pinfunction "2_2") (pintype "passive"))
      (node (ref "R211") (pin "1") (pinfunction "1_1") (pintype "passive"))
      (node (ref "R213") (pin "1") (pinfunction "1_1") (pintype "passive"))
    )
    (net (code "20") (name "BP4") (class "Default")
      (node (ref "L201") (pin "2") (pinfunction "2_2") (pintype "passive"))
      (node (ref "Q201") (pin "G") (pinfunction "G_G") (pintype "passive"))
      (node (ref "R213") (pin "2") (pinfunction "2_2") (pintype "passive"))
      (node (ref "R215") (pin "1") (pinfunction "1_1") (pintype "passive"))
      (node (ref "R217") (pin "1") (pinfunction "1_1") (pintype "passive"))
      (node (ref "R218") (pin "1") (pinfunction "1_1") (pintype "passive"))
      (node (ref "TP7") (pin "TP") (pinfunction "1_TP") (pintype "passive"))
    )
    (net (code "21") (name "BP5") (class "Default")
      (node (ref "Q201") (pin "S") (pinfunction "S_S") (pintype "passive"))
      (node (ref "R221") (pin "1") (pinfunction "1_1") (pintype "passive"))
      (node (ref "R223") (pin "1") (pinfunction "1_1") (pintype "passive"))
      (node (ref "R225") (pin "1") (pinfunction "1_1") (pintype "passive"))
      (node (ref "R227") (pin "1") (pinfunction "1_1") (pintype "passive"))
      (node (ref "R46") (pin "2") (pinfunction "2_2") (pintype "passive"))
      (node (ref "TP8") (pin "TP") (pinfunction "1_TP") (pintype "passive"))
    )
    (net (code "22") (name "DRAINS_NEG") (class "Default")
      (node (ref "C113") (pin "2") (pinfunction "2_2") (pintype "passive"))
      (node (ref "C117") (pin "2") (pinfunction "2_2") (pintype "passive"))
      (node (ref "C210") (pin "2") (pinfunction "2_2") (pintype "passive"))
      (node (ref "L104") (pin "1") (pinfunction "1_1") (pintype "passive"))
      (node (ref "Q102") (pin "D") (pinfunction "D_D") (pintype "passive"))
      (node (ref "Q202") (pin "D") (pinfunction "D_D") (pintype "passive"))
      (node (ref "T102") (pin "8") (pinfunction "F5_8") (pintype "passive"))
      (node (ref "TP4") (pin "TP") (pinfunction "1_TP") (pintype "passive"))
    )
    (net (code "23") (name "DRAINS_POS") (class "Default")
      (node (ref "C112") (pin "2") (pinfunction "2_2") (pintype "passive"))
      (node (ref "C116") (pin "2") (pinfunction "2_2") (pintype "passive"))
      (node (ref "C209") (pin "2") (pinfunction "2_2") (pintype "passive"))
      (node (ref "L103") (pin "1") (pinfunction "1_1") (pintype "passive"))
      (node (ref "Q101") (pin "D") (pinfunction "D_D") (pintype "passive"))
      (node (ref "Q201") (pin "D") (pinfunction "D_D") (pintype "passive"))
      (node (ref "T102") (pin "6") (pinfunction "S6_6") (pintype "passive"))
      (node (ref "TP2") (pin "TP") (pinfunction "1_TP") (pintype "passive"))
    )
    (net (code "24") (name "MIDBIAS") (class "Default")
      (node (ref "C27") (pin "1") (pinfunction "1_1") (pintype "passive"))
      (node (ref "IC1") (pin "3") (pinfunction "+IN_3") (pintype "input"))
      (node (ref "IC2") (pin "3") (pinfunction "+IN_3") (pintype "input"))
      (node (ref "R49") (pin "2") (pinfunction "2_2") (pintype "passive"))
      (node (ref "R50") (pin "1") (pinfunction "1_1") (pintype "passive"))
    )
    (net (code "25") (name "Net-(C7-Pad1)") (class "Default")
      (node (ref "C7") (pin "1") (pinfunction "1_1") (pintype "passive"))
      (node (ref "R14") (pin "2") (pinfunction "2_2") (pintype "passive"))
    )
    (net (code "26") (name "Net-(C9-Pad1)") (class "Default")
      (node (ref "C9") (pin "1") (pinfunction "1_1") (pintype "passive"))
      (node (ref "R23") (pin "2") (pinfunction "2_2") (pintype "passive"))
    )
    (net (code "27") (name "Net-(C10-Pad1)") (class "Default")
      (node (ref "C10") (pin "1") (pinfunction "1_1") (pintype "passive"))
      (node (ref "R22") (pin "2") (pinfunction "2_2") (pintype "passive"))
    )
    (net (code "28") (name "Net-(C12-Pad1)") (class "Default")
      (node (ref "C12") (pin "1") (pinfunction "1_1") (pintype "passive"))
      (node (ref "R17") (pin "1") (pinfunction "1_1") (pintype "passive"))
      (node (ref "R25") (pin "2") (pinfunction "2_2") (pintype "passive"))
    )
    (net (code "29") (name "Net-(C13-Pad1)") (class "Default")
      (node (ref "C13") (pin "1") (pinfunction "1_1") (pintype "passive"))
      (node (ref "R41") (pin "2") (pinfunction "2_2") (pintype "passive"))
    )
    (net (code "30") (name "Net-(C14-Pad1)") (class "Default")
      (node (ref "C14") (pin "1") (pinfunction "1_1") (pintype "passive"))
      (node (ref "R40") (pin "1") (pinfunction "1_1") (pintype "passive"))
    )
    (net (code "31") (name "Net-(C17-Pad1)") (class "Default")
      (node (ref "C17") (pin "1") (pinfunction "1_1") (pintype "passive"))
      (node (ref "R28") (pin "1") (pinfunction "1_1") (pintype "passive"))
    )
    (net (code "32") (name "Net-(C17-Pad2)") (class "Default")
      (node (ref "C17") (pin "2") (pinfunction "2_2") (pintype "passive"))
      (node (ref "R30") (pin "1") (pinfunction "1_1") (pintype "passive"))
      (node (ref "X2") (pin "1") (pinfunction "1_1") (pintype "passive"))
    )
    (net (code "33") (name "Net-(C19-Pad1)") (class "Default")
      (node (ref "C19") (pin "1") (pinfunction "1_1") (pintype "passive"))
      (node (ref "R31") (pin "1") (pinfunction "1_1") (pintype "passive"))
    )
    (net (code "34") (name "Net-(C20-Pad1)") (class "Default")
      (node (ref "C20") (pin "1") (pinfunction "1_1") (pintype "passive"))
      (node (ref "JP2") (pin "3") (pinfunction "3_3") (pintype "passive"))
    )
    (net (code "35") (name "Net-(C20-Pad2)") (class "Default")
      (node (ref "C20") (pin "2") (pinfunction "2_2") (pintype "passive"))
      (node (ref "R29") (pin "2") (pinfunction "2_2") (pintype "passive"))
    )
    (net (code "36") (name "Net-(C104-Pad1)") (class "Default")
      (node (ref "C104") (pin "1") (pinfunction "1_1") (pintype "passive"))
      (node (ref "R108") (pin "2") (pinfunction "2_2") (pintype "passive"))
      (node (ref "R109") (pin "1") (pinfunction "1_1") (pintype "passive"))
    )
    (net (code "37") (name "Net-(C106-Pad1)") (class "Default")
      (node (ref "C106") (pin "1") (pinfunction "1_1") (pintype "passive"))
      (node (ref "R110") (pin "2") (pinfunction "2_2") (pintype "passive"))
      (node (ref "R111") (pin "1") (pinfunction "1_1") (pintype "passive"))
    )
    (net (code "38") (name "Net-(C108-Pad1)") (class "Default")
      (node (ref "C108") (pin "1") (pinfunction "1_1") (pintype "passive"))
      (node (ref "R112") (pin "2") (pinfunction "2_2") (pintype "passive"))
    )
    (net (code "39") (name "Net-(C109-Pad1)") (class "Default")
      (node (ref "C109") (pin "1") (pinfunction "1_1") (pintype "passive"))
      (node (ref "R113") (pin "2") (pinfunction "2_2") (pintype "passive"))
    )
    (net (code "40") (name "Net-(C110-Pad1)") (class "Default")
      (node (ref "C110") (pin "1") (pinfunction "1_1") (pintype "passive"))
      (node (ref "R116") (pin "2") (pinfunction "2_2") (pintype "passive"))
    )
    (net (code "41") (name "Net-(C111-Pad1)") (class "Default")
      (node (ref "C111") (pin "1") (pinfunction "1_1") (pintype "passive"))
      (node (ref "R117") (pin "2") (pinfunction "2_2") (pintype "passive"))
    )
    (net (code "42") (name "Net-(C112-Pad1)") (class "Default")
      (node (ref "C112") (pin "1") (pinfunction "1_1") (pintype "passive"))
      (node (ref "R118") (pin "2") (pinfunction "2_2") (pintype "passive"))
      (node (ref "R119") (pin "2") (pinfunction "2_2") (pintype "passive"))
    )
    (net (code "43") (name "Net-(C113-Pad1)") (class "Default")
      (node (ref "C113") (pin "1") (pinfunction "1_1") (pintype "passive"))
      (node (ref "R120") (pin "2") (pinfunction "2_2") (pintype "passive"))
      (node (ref "R121") (pin "2") (pinfunction "2_2") (pintype "passive"))
    )
    (net (code "44") (name "Net-(C118-Pad1)") (class "Default")
      (node (ref "C118") (pin "1") (pinfunction "1_1") (pintype "passive"))
      (node (ref "R24") (pin "2") (pinfunction "2_2") (pintype "passive"))
      (node (ref "R53") (pin "2") (pinfunction "2_2") (pintype "passive"))
      (node (ref "R54") (pin "2") (pinfunction "2_2") (pintype "passive"))
    )
    (net (code "45") (name "Net-(C118-Pad2)") (class "Default")
      (node (ref "C118") (pin "2") (pinfunction "2_2") (pintype "passive"))
      (node (ref "X4") (pin "1") (pinfunction "1_1") (pintype "passive"))
    )
    (net (code "46") (name "Net-(C201-Pad1)") (class "Default")
      (node (ref "C201") (pin "1") (pinfunction "1_1") (pintype "passive"))
      (node (ref "R207") (pin "2") (pinfunction "2_2") (pintype "passive"))
      (node (ref "R208") (pin "1") (pinfunction "1_1") (pintype "passive"))
    )
    (net (code "47") (name "Net-(C203-Pad1)") (class "Default")
      (node (ref "C203") (pin "1") (pinfunction "1_1") (pintype "passive"))
      (node (ref "R209") (pin "2") (pinfunction "2_2") (pintype "passive"))
      (node (ref "R210") (pin "1") (pinfunction "1_1") (pintype "passive"))
    )
    (net (code "48") (name "Net-(C205-Pad1)") (class "Default")
      (node (ref "C205") (pin "1") (pinfunction "1_1") (pintype "passive"))
      (node (ref "R211") (pin "2") (pinfunction "2_2") (pintype "passive"))
    )
    (net (code "49") (name "Net-(C206-Pad1)") (class "Default")
      (node (ref "C206") (pin "1") (pinfunction "1_1") (pintype "passive"))
      (node (ref "R212") (pin "2") (pinfunction "2_2") (pintype "passive"))
    )
    (net (code "50") (name "Net-(C207-Pad1)") (class "Default")
      (node (ref "C207") (pin "1") (pinfunction "1_1") (pintype "passive"))
      (node (ref "R215") (pin "2") (pinfunction "2_2") (pintype "passive"))
    )
    (net (code "51") (name "Net-(C208-Pad1)") (class "Default")
      (node (ref "C208") (pin "1") (pinfunction "1_1") (pintype "passive"))
      (node (ref "R216") (pin "2") (pinfunction "2_2") (pintype "passive"))
    )
    (net (code "52") (name "Net-(C209-Pad1)") (class "Default")
      (node (ref "C209") (pin "1") (pinfunction "1_1") (pintype "passive"))
      (node (ref "R217") (pin "2") (pinfunction "2_2") (pintype "passive"))
      (node (ref "R218") (pin "2") (pinfunction "2_2") (pintype "passive"))
    )
    (net (code "53") (name "Net-(C210-Pad1)") (class "Default")
      (node (ref "C210") (pin "1") (pinfunction "1_1") (pintype "passive"))
      (node (ref "R219") (pin "2") (pinfunction "2_2") (pintype "passive"))
      (node (ref "R220") (pin "2") (pinfunction "2_2") (pintype "passive"))
    )
    (net (code "54") (name "Net-(C302-Pad1)") (class "Default")
      (node (ref "C302") (pin "1") (pinfunction "1_1") (pintype "passive"))
      (node (ref "R313") (pin "1") (pinfunction "1_1") (pintype "passive"))
    )
    (net (code "55") (name "Net-(C304-Pad1)") (class "Default")
      (node (ref "C304") (pin "1") (pinfunction "1_1") (pintype "passive"))
      (node (ref "R314") (pin "2") (pinfunction "2_2") (pintype "passive"))
    )
    (net (code "56") (name "Net-(C405-Pad1)") (class "Default")
      (node (ref "C405") (pin "1") (pinfunction "1_1") (pintype "passive"))
      (node (ref "L401") (pin "2") (pinfunction "2_2") (pintype "passive"))
      (node (ref "L402") (pin "1") (pinfunction "1_1") (pintype "passive"))
      (node (ref "R404") (pin "1") (pinfunction "1_1") (pintype "passive"))
      (node (ref "R405") (pin "1") (pinfunction "1_1") (pintype "passive"))
    )
    (net (code "57") (name "Net-(D1-C1)") (class "Default")
      (node (ref "D1") (pin "K") (pinfunction "C1_K") (pintype "passive"))
      (node (ref "D3") (pin "A") (pinfunction "A1_A") (pintype "passive"))
      (node (ref "IC7") (pin "1") (pinfunction "I0_1") (pintype "input"))
      (node (ref "R304") (pin "2") (pinfunction "2_2") (pintype "passive"))
      (node (ref "R307") (pin "1") (pinfunction "1_1") (pintype "passive"))
    )
    (net (code "58") (name "Net-(D2-A1)") (class "Default")
      (node (ref "D2") (pin "A") (pinfunction "A1_A") (pintype "passive"))
      (node (ref "R7") (pin "2") (pinfunction "2_2") (pintype "passive"))
    )
    (net (code "59") (name "Net-(D2-C1)") (class "Default")
      (node (ref "C3") (pin "1") (pinfunction "1_1") (pintype "passive"))
      (node (ref "D2") (pin "K") (pinfunction "C1_K") (pintype "passive"))
      (node (ref "IC3") (pin "2") (pinfunction "-IN_2") (pintype "input"))
      (node (ref "R4") (pin "2") (pinfunction "2_2") (pintype "passive"))
    )
    (net (code "60") (name "Net-(D4-A1)") (class "Default")
      (node (ref "C2") (pin "1") (pinfunction "1_1") (pintype "passive"))
      (node (ref "D4") (pin "A") (pinfunction "A1_A") (pintype "passive"))
      (node (ref "IC3") (pin "6") (pinfunction "-IN_6") (pintype "input"))
      (node (ref "R1") (pin "2") (pinfunction "2_2") (pintype "passive"))
    )
    (net (code "61") (name "Net-(D4-C1)") (class "Default")
      (node (ref "D4") (pin "K") (pinfunction "C1_K") (pintype "passive"))
      (node (ref "IC5") (pin "2") (pinfunction "I1_2") (pintype "input"))
      (node (ref "IC7") (pin "4") (pinfunction "O_4") (pintype "output"))
      (node (ref "LED2") (pin "A") (pinfunction "A_A") (pintype "passive"))
      (node (ref "R1") (pin "1") (pinfunction "1_1") (pintype "passive"))
      (node (ref "R4") (pin "1") (pinfunction "1_1") (pintype "passive"))
      (node (ref "R7") (pin "1") (pinfunction "1_1") (pintype "passive"))
    )
    (net (code "62") (name "Net-(IC1--IN)") (class "Default")
      (node (ref "C16") (pin "2") (pinfunction "2_2") (pintype "passive"))
      (node (ref "IC1") (pin "2") (pinfunction "-IN_2") (pintype "input"))
      (node (ref "R27") (pin "1") (pinfunction "1_1") (pintype "passive"))
      (node (ref "R28") (pin "2") (pinfunction "2_2") (pintype "passive"))
    )
    (net (code "63") (name "Net-(IC1-OUT)") (class "Default")
      (node (ref "C16") (pin "1") (pinfunction "1_1") (pintype "passive"))
      (node (ref "C19") (pin "2") (pinfunction "2_2") (pintype "passive"))
      (node (ref "IC1") (pin "6") (pinfunction "OUT_6") (pintype "output"))
      (node (ref "R27") (pin "2") (pinfunction "2_2") (pintype "passive"))
      (node (ref "R32") (pin "1") (pinfunction "1_1") (pintype "passive"))
    )
    (net (code "64") (name "Net-(IC2--IN)") (class "Default")
      (node (ref "C18") (pin "2") (pinfunction "2_2") (pintype "passive"))
      (node (ref "IC2") (pin "2") (pinfunction "-IN_2") (pintype "input"))
      (node (ref "R20") (pin "1") (pinfunction "1_1") (pintype "passive"))
      (node (ref "R31") (pin "2") (pinfunction "2_2") (pintype "passive"))
    )
    (net (code "65") (name "Net-(IC2-OUT)") (class "Default")
      (node (ref "C18") (pin "1") (pinfunction "1_1") (pintype "passive"))
      (node (ref "IC2") (pin "6") (pinfunction "OUT_6") (pintype "output"))
      (node (ref "R20") (pin "2") (pinfunction "2_2") (pintype "passive"))
      (node (ref "R29") (pin "1") (pinfunction "1_1") (pintype "passive"))
    )
    (net (code "66") (name "Net-(IC3A-+IN)") (class "Default")
      (node (ref "IC3") (pin "3") (pinfunction "+IN_3") (pintype "input"))
      (node (ref "R5") (pin "1") (pinfunction "1_1") (pintype "passive"))
      (node (ref "R6") (pin "2") (pinfunction "2_2") (pintype "passive"))
    )
    (net (code "67") (name "Net-(IC3B-+IN)") (class "Default")
      (node (ref "IC3") (pin "5") (pinfunction "+IN_5") (pintype "input"))
      (node (ref "R2") (pin "1") (pinfunction "1_1") (pintype "passive"))
      (node (ref "R3") (pin "2") (pinfunction "2_2") (pintype "passive"))
    )
    (net (code "68") (name "Net-(IC6A-PRE)") (class "Default")
      (node (ref "C5") (pin "1") (pinfunction "1_1") (pintype "passive"))
      (node (ref "IC6") (pin "4") (pinfunction "PRE_4") (pintype "input"))
      (node (ref "R9") (pin "2") (pinfunction "2_2") (pintype "passive"))
    )
    (net (code "69") (name "Net-(J402-Pad3)") (class "Default")
      (node (ref "J402") (pin "3") (pinfunction "3_3") (pintype "passive"))
      (node (ref "R408") (pin "2") (pinfunction "2_2") (pintype "passive"))
    )
    (net (code "70") (name "Net-(JP2-Pad1)") (class "Default")
      (node (ref "JP2") (pin "1") (pinfunction "1_1") (pintype "passive"))
      (node (ref "R32") (pin "2") (pinfunction "2_2") (pintype "passive"))
    )
    (net (code "71") (name "Net-(JP301-Pad1)") (class "Default")
      (node (ref "JP301") (pin "1") (pinfunction "1_1") (pintype "passive"))
      (node (ref "R303") (pin "1") (pinfunction "1_1") (pintype "passive"))
    )
    (net (code "72") (name "Net-(JP301-Pad2)") (class "Default")
      (node (ref "JP301") (pin "2") (pinfunction "2_2") (pintype "passive"))
      (node (ref "R302") (pin "1") (pinfunction "1_1") (pintype "passive"))
    )
    (net (code "73") (name "Net-(LED1-C)") (class "Default")
      (node (ref "LED1") (pin "K") (pinfunction "C_K") (pintype "passive"))
      (node (ref "R12") (pin "1") (pinfunction "1_1") (pintype "passive"))
    )
    (net (code "74") (name "Net-(LED2-C)") (class "Default")
      (node (ref "LED2") (pin "K") (pinfunction "C_K") (pintype "passive"))
      (node (ref "R52") (pin "1") (pinfunction "1_1") (pintype "passive"))
    )
    (net (code "75") (name "Net-(LED402-PadA)") (class "Default")
      (node (ref "LED402") (pin "A") (pinfunction "A_A") (pintype "passive"))
      (node (ref "R407") (pin "2") (pinfunction "2_2") (pintype "passive"))
    )
    (net (code "76") (name "Net-(Q2-D)") (class "Default")
      (node (ref "Q2") (pin "3") (pinfunction "D_3") (pintype "passive"))
      (node (ref "R43") (pin "2") (pinfunction "2_2") (pintype "passive"))
      (node (ref "U1") (pin "5") (pinfunction "+IN_5") (pintype "input"))
    )
    (net (code "77") (name "Net-(Q3-B)") (class "Default")
      (node (ref "Q3") (pin "1") (pinfunction "B_1") (pintype "passive"))
      (node (ref "Q4") (pin "1") (pinfunction "B_1") (pintype "passive"))
      (node (ref "R36") (pin "2") (pinfunction "2_2") (pintype "passive"))
      (node (ref "R37") (pin "1") (pinfunction "1_1") (pintype "passive"))
    )
    (net (code "78") (name "Net-(Q6-B)") (class "Default")
      (node (ref "C30") (pin "1") (pinfunction "1_1") (pintype "passive"))
      (node (ref "Q6") (pin "G") (pinfunction "B_G") (pintype "passive"))
      (node (ref "R55") (pin "2") (pinfunction "2_2") (pintype "passive"))
      (node (ref "U2") (pin "3") (pinfunction "C_3") (pintype "passive"))
    )
    (net (code "79") (name "Net-(Q301-D)") (class "Default")
      (node (ref "Q301") (pin "3") (pinfunction "D_3") (pintype "passive"))
      (node (ref "R308") (pin "2") (pinfunction "2_2") (pintype "passive"))
      (node (ref "U302") (pin "5") (pinfunction "+IN_5") (pintype "input"))
    )
    (net (code "80") (name "Net-(Q302-B)") (class "Default")
      (node (ref "Q302") (pin "1") (pinfunction "B_1") (pintype "passive"))
      (node (ref "Q303") (pin "1") (pinfunction "B_1") (pintype "passive"))
      (node (ref "R315") (pin "2") (pinfunction "2_2") (pintype "passive"))
      (node (ref "R316") (pin "1") (pinfunction "1_1") (pintype "passive"))
    )
    (net (code "81") (name "Net-(R13-S)") (class "Default")
      (node (ref "R13") (pin "2") (pinfunction "S_2") (pintype "passive"))
      (node (ref "R3") (pin "1") (pinfunction "1_1") (pintype "passive"))
    )
    (net (code "82") (name "Net-(R33-S)") (class "Default")
      (node (ref "R33") (pin "2") (pinfunction "S_2") (pintype "passive"))
      (node (ref "R6") (pin "1") (pinfunction "1_1") (pintype "passive"))
    )
    (net (code "83") (name "Net-(R34-S)") (class "Default")
      (node (ref "C6") (pin "1") (pinfunction "1_1") (pintype "passive"))
      (node (ref "R34") (pin "2") (pinfunction "S_2") (pintype "passive"))
      (node (ref "U1") (pin "12") (pinfunction "+IN_12") (pintype "input"))
    )
    (net (code "84") (name "Net-(R44-Pad1)") (class "Default")
      (node (ref "R44") (pin "1") (pinfunction "1_1") (pintype "passive"))
      (node (ref "R45") (pin "1") (pinfunction "1_1") (pintype "passive"))
      (node (ref "R46") (pin "1") (pinfunction "1_1") (pintype "passive"))
      (node (ref "R47") (pin "1") (pinfunction "1_1") (pintype "passive"))
      (node (ref "R51") (pin "2") (pinfunction "2_2") (pintype "passive"))
    )
    (net (code "85") (name "Net-(R301-S)") (class "Default")
      (node (ref "C301") (pin "1") (pinfunction "1_1") (pintype "passive"))
      (node (ref "R301") (pin "2") (pinfunction "S_2") (pintype "passive"))
      (node (ref "U302") (pin "12") (pinfunction "+IN_12") (pintype "input"))
    )
    (net (code "86") (name "Net-(R304-Pad1)") (class "Default")
      (node (ref "R304") (pin "1") (pinfunction "1_1") (pintype "passive"))
      (node (ref "X1") (pin "1") (pinfunction "1_1") (pintype "passive"))
    )
    (net (code "87") (name "Net-(T1-F1)") (class "Default")
      (node (ref "R101") (pin "1") (pinfunction "1_1") (pintype "passive"))
      (node (ref "T1") (pin "12") (pinfunction "F1_12") (pintype "passive"))
      (node (ref "T1") (pin "2") (pinfunction "S2_2") (pintype "passive"))
    )
    (net (code "88") (name "Net-(T1-F4)") (class "Default")
      (node (ref "T1") (pin "3") (pinfunction "S3_3") (pintype "passive"))
      (node (ref "T1") (pin "9") (pinfunction "F4_9") (pintype "passive"))
    )
    (net (code "89") (name "Net-(T1-F5)") (class "Default")
      (node (ref "T1") (pin "4") (pinfunction "S4_4") (pintype "passive"))
      (node (ref "T1") (pin "8") (pinfunction "F5_8") (pintype "passive"))
    )
    (net (code "90") (name "Net-(T1-F6)") (class "Default")
      (node (ref "T1") (pin "5") (pinfunction "S5_5") (pintype "passive"))
      (node (ref "T1") (pin "7") (pinfunction "F6_7") (pintype "passive"))
    )
    (net (code "91") (name "Net-(T1-S6)") (class "Default")
      (node (ref "C1") (pin "1") (pinfunction "1_1") (pintype "passive"))
      (node (ref "T1") (pin "6") (pinfunction "S6_6") (pintype "passive"))
    )
    (net (code "92") (name "Net-(T102-F1)") (class "Default")
      (node (ref "R53") (pin "1") (pinfunction "1_1") (pintype "passive"))
      (node (ref "T102") (pin "12") (pinfunction "F1_12") (pintype "passive"))
      (node (ref "T102") (pin "2") (pinfunction "S2_2") (pintype "passive"))
    )
    (net (code "93") (name "Net-(T102-F2)") (class "Default")
      (node (ref "R24") (pin "1") (pinfunction "1_1") (pintype "passive"))
      (node (ref "T102") (pin "11") (pinfunction "F2_11") (pintype "passive"))
      (node (ref "T102") (pin "3") (pinfunction "S3_3") (pintype "passive"))
    )
    (net (code "94") (name "Net-(T102-F3)") (class "Default")
      (node (ref "T102") (pin "10") (pinfunction "F3_10") (pintype "passive"))
      (node (ref "T102") (pin "4") (pinfunction "S4_4") (pintype "passive"))
    )
    (net (code "95") (name "Net-(T102-F6)") (class "Default")
      (node (ref "R132") (pin "2") (pinfunction "2_2") (pintype "passive"))
      (node (ref "T102") (pin "5") (pinfunction "S5_5") (pintype "passive"))
      (node (ref "T102") (pin "7") (pinfunction "F6_7") (pintype "passive"))
    )
    (net (code "96") (name "Net-(T102-S1)") (class "Default")
      (node (ref "R54") (pin "1") (pinfunction "1_1") (pintype "passive"))
      (node (ref "T102") (pin "1") (pinfunction "S1_1") (pintype "passive"))
    )
    (net (code "97") (name "Net-(TP12-1)") (class "Default")
      (node (ref "R310") (pin "1") (pinfunction "1_1") (pintype "passive"))
      (node (ref "TP12") (pin "TP") (pinfunction "1_TP") (pintype "passive"))
      (node (ref "U302") (pin "6") (pinfunction "-IN_6") (pintype "input"))
      (node (ref "U302") (pin "7") (pinfunction "OUT_7") (pintype "output"))
    )
    (net (code "98") (name "Net-(TP13-1)") (class "Default")
      (node (ref "R306") (pin "2") (pinfunction "2_2") (pintype "passive"))
      (node (ref "TP13") (pin "TP") (pinfunction "1_TP") (pintype "passive"))
      (node (ref "U302") (pin "13") (pinfunction "-IN_13") (pintype "input"))
      (node (ref "U302") (pin "14") (pinfunction "OUT_14") (pintype "output"))
    )
    (net (code "99") (name "Net-(TP22-1)") (class "Default")
      (node (ref "R43") (pin "1") (pinfunction "1_1") (pintype "passive"))
      (node (ref "TP22") (pin "TP") (pinfunction "1_TP") (pintype "passive"))
      (node (ref "U1") (pin "13") (pinfunction "-IN_13") (pintype "input"))
      (node (ref "U1") (pin "14") (pinfunction "OUT_14") (pintype "output"))
    )
    (net (code "100") (name "Net-(TP25-1)") (class "Default")
      (node (ref "R35") (pin "1") (pinfunction "1_1") (pintype "passive"))
      (node (ref "TP25") (pin "TP") (pinfunction "1_TP") (pintype "passive"))
      (node (ref "U1") (pin "6") (pinfunction "-IN_6") (pintype "input"))
      (node (ref "U1") (pin "7") (pinfunction "OUT_7") (pintype "output"))
    )
    (net (code "101") (name "Net-(U1A-+IN)") (class "Default")
      (node (ref "C15") (pin "1") (pinfunction "1_1") (pintype "passive"))
      (node (ref "R35") (pin "2") (pinfunction "2_2") (pintype "passive"))
      (node (ref "R42") (pin "1") (pinfunction "1_1") (pintype "passive"))
      (node (ref "U1") (pin "3") (pinfunction "+IN_3") (pintype "input"))
    )
    (net (code "102") (name "Net-(U1A--IN)") (class "Default")
      (node (ref "C13") (pin "2") (pinfunction "2_2") (pintype "passive"))
      (node (ref "R38") (pin "1") (pinfunction "1_1") (pintype "passive"))
      (node (ref "R39") (pin "2") (pinfunction "2_2") (pintype "passive"))
      (node (ref "R40") (pin "2") (pinfunction "2_2") (pintype "passive"))
      (node (ref "R48") (pin "1") (pinfunction "1_1") (pintype "passive"))
      (node (ref "U1") (pin "2") (pinfunction "-IN_2") (pintype "input"))
    )
    (net (code "103") (name "Net-(U1A-OUT)") (class "Default")
      (node (ref "R36") (pin "1") (pinfunction "1_1") (pintype "passive"))
      (node (ref "R41") (pin "1") (pinfunction "1_1") (pintype "passive"))
      (node (ref "U1") (pin "1") (pinfunction "OUT_1") (pintype "output"))
    )
    (net (code "104") (name "Net-(U1C--IN)") (class "Default")
      (node (ref "U1") (pin "8") (pinfunction "OUT_8") (pintype "output"))
      (node (ref "U1") (pin "9") (pinfunction "-IN_9") (pintype "input"))
    )
    (net (code "105") (name "Net-(U2-R)") (class "Default")
      (node (ref "C30") (pin "2") (pinfunction "2_2") (pintype "passive"))
      (node (ref "R56") (pin "1") (pinfunction "1_1") (pintype "passive"))
      (node (ref "R57") (pin "2") (pinfunction "2_2") (pintype "passive"))
      (node (ref "U2") (pin "1") (pinfunction "R_1") (pintype "passive"))
    )
    (net (code "106") (name "Net-(U302A-+IN)") (class "Default")
      (node (ref "C303") (pin "1") (pinfunction "1_1") (pintype "passive"))
      (node (ref "R310") (pin "2") (pinfunction "2_2") (pintype "passive"))
      (node (ref "R311") (pin "1") (pinfunction "1_1") (pintype "passive"))
      (node (ref "U302") (pin "3") (pinfunction "+IN_3") (pintype "input"))
    )
    (net (code "107") (name "Net-(U302A--IN)") (class "Default")
      (node (ref "C304") (pin "2") (pinfunction "2_2") (pintype "passive"))
      (node (ref "R312") (pin "2") (pinfunction "2_2") (pintype "passive"))
      (node (ref "R313") (pin "2") (pinfunction "2_2") (pintype "passive"))
      (node (ref "R317") (pin "1") (pinfunction "1_1") (pintype "passive"))
      (node (ref "R51") (pin "1") (pinfunction "1_1") (pintype "passive"))
      (node (ref "U302") (pin "2") (pinfunction "-IN_2") (pintype "input"))
    )
    (net (code "108") (name "Net-(U302A-OUT)") (class "Default")
      (node (ref "R314") (pin "1") (pinfunction "1_1") (pintype "passive"))
      (node (ref "R315") (pin "1") (pinfunction "1_1") (pintype "passive"))
      (node (ref "U302") (pin "1") (pinfunction "OUT_1") (pintype "output"))
    )
    (net (code "109") (name "Net-(U302C-+IN)") (class "Default")
      (node (ref "R303") (pin "2") (pinfunction "2_2") (pintype "passive"))
      (node (ref "R306") (pin "1") (pinfunction "1_1") (pintype "passive"))
      (node (ref "U302") (pin "10") (pinfunction "+IN_10") (pintype "input"))
    )
    (net (code "110") (name "Net-(U302C--IN)") (class "Default")
      (node (ref "JP302") (pin "1") (pinfunction "1_1") (pintype "passive"))
      (node (ref "R302") (pin "2") (pinfunction "2_2") (pintype "passive"))
      (node (ref "R305") (pin "1") (pinfunction "1_1") (pintype "passive"))
      (node (ref "U302") (pin "9") (pinfunction "-IN_9") (pintype "input"))
    )
    (net (code "111") (name "Net-(U302C-OUT)") (class "Default")
      (node (ref "JP302") (pin "2") (pinfunction "2_2") (pintype "passive"))
      (node (ref "R305") (pin "2") (pinfunction "2_2") (pintype "passive"))
      (node (ref "R308") (pin "1") (pinfunction "1_1") (pintype "passive"))
      (node (ref "U302") (pin "8") (pinfunction "OUT_8") (pintype "output"))
    )
    (net (code "112") (name "READY") (class "Default")
      (node (ref "IC5") (pin "1") (pinfunction "I0_1") (pintype "input"))
      (node (ref "IC6") (pin "5") (pinfunction "Q_5") (pintype "output"))
    )
    (net (code "113") (name "RESET") (class "Default")
      (node (ref "C4") (pin "1") (pinfunction "1_1") (pintype "passive"))
      (node (ref "IC6") (pin "3") (pinfunction "CLK_3") (pintype "input"))
      (node (ref "R8") (pin "1") (pinfunction "1_1") (pintype "passive"))
      (node (ref "SW2") (pin "3") (pinfunction "S1_3") (pintype "passive"))
    )
    (net (code "114") (name "S1_BP2") (class "Default")
      (node (ref "C11") (pin "2") (pinfunction "2_2") (pintype "passive"))
      (node (ref "R18") (pin "1") (pinfunction "1_1") (pintype "passive"))
      (node (ref "R19") (pin "2") (pinfunction "2_2") (pintype "passive"))
    )
    (net (code "115") (name "S1_BP3") (class "Default")
      (node (ref "C11") (pin "1") (pinfunction "1_1") (pintype "passive"))
      (node (ref "L2") (pin "1") (pinfunction "1_1") (pintype "passive"))
      (node (ref "R17") (pin "2") (pinfunction "2_2") (pintype "passive"))
      (node (ref "R21") (pin "1") (pinfunction "1_1") (pintype "passive"))
      (node (ref "R22") (pin "1") (pinfunction "1_1") (pintype "passive"))
    )
    (net (code "116") (name "S1_BP4") (class "Default")
      (node (ref "L2") (pin "2") (pinfunction "2_2") (pintype "passive"))
      (node (ref "Q1") (pin "G") (pinfunction "G_G") (pintype "passive"))
      (node (ref "R14") (pin "1") (pinfunction "1_1") (pintype "passive"))
      (node (ref "R21") (pin "2") (pinfunction "2_2") (pintype "passive"))
      (node (ref "R23") (pin "1") (pinfunction "1_1") (pintype "passive"))
      (node (ref "TP20") (pin "TP") (pinfunction "1_TP") (pintype "passive"))
    )
    (net (code "117") (name "S1_BP5") (class "Default")
      (node (ref "Q1") (pin "S") (pinfunction "S_S") (pintype "passive"))
      (node (ref "R15") (pin "1") (pinfunction "1_1") (pintype "passive"))
      (node (ref "R16") (pin "1") (pinfunction "1_1") (pintype "passive"))
      (node (ref "R48") (pin "2") (pinfunction "2_2") (pintype "passive"))
      (node (ref "TP21") (pin "TP") (pinfunction "1_TP") (pintype "passive"))
    )
    (net (code "118") (name "S2_BP1") (class "Default")
      (node (ref "JP2") (pin "2") (pinfunction "2_2") (pintype "passive"))
      (node (ref "R19") (pin "1") (pinfunction "1_1") (pintype "passive"))
      (node (ref "R26") (pin "1") (pinfunction "1_1") (pintype "passive"))
      (node (ref "TP27") (pin "TP") (pinfunction "1_TP") (pintype "passive"))
    )
    (net (code "119") (name "S2_DP") (class "Default")
      (node (ref "C1") (pin "2") (pinfunction "2_2") (pintype "passive"))
      (node (ref "C7") (pin "2") (pinfunction "2_2") (pintype "passive"))
      (node (ref "C8") (pin "2") (pinfunction "2_2") (pintype "passive"))
      (node (ref "L1") (pin "1") (pinfunction "1_1") (pintype "passive"))
      (node (ref "Q1") (pin "D") (pinfunction "D_D") (pintype "passive"))
    )
    (net (code "120") (name "S2_GBIAS") (class "Default")
      (node (ref "Q3") (pin "2") (pinfunction "E_2") (pintype "passive"))
      (node (ref "Q4") (pin "2") (pinfunction "E_2") (pintype "passive"))
      (node (ref "R25") (pin "1") (pinfunction "1_1") (pintype "passive"))
      (node (ref "R37") (pin "2") (pinfunction "2_2") (pintype "passive"))
      (node (ref "R38") (pin "2") (pinfunction "2_2") (pintype "passive"))
      (node (ref "TP23") (pin "TP") (pinfunction "1_TP") (pintype "passive"))
    )
    (net (code "121") (name "S3_GBIAS") (class "Default")
      (node (ref "Q302") (pin "2") (pinfunction "E_2") (pintype "passive"))
      (node (ref "Q303") (pin "2") (pinfunction "E_2") (pintype "passive"))
      (node (ref "R108") (pin "1") (pinfunction "1_1") (pintype "passive"))
      (node (ref "R110") (pin "1") (pinfunction "1_1") (pintype "passive"))
      (node (ref "R207") (pin "1") (pinfunction "1_1") (pintype "passive"))
      (node (ref "R209") (pin "1") (pinfunction "1_1") (pintype "passive"))
      (node (ref "R316") (pin "2") (pinfunction "2_2") (pintype "passive"))
      (node (ref "R317") (pin "2") (pinfunction "2_2") (pintype "passive"))
      (node (ref "TP11") (pin "TP") (pinfunction "1_TP") (pintype "passive"))
    )
    (net (code "122") (name "V+") (class "Default")
      (node (ref "C21") (pin "1") (pinfunction "1_1") (pintype "passive"))
      (node (ref "C305") (pin "1") (pinfunction "1_1") (pintype "passive"))
      (node (ref "C406") (pin "1") (pinfunction "1_1") (pintype "passive"))
      (node (ref "C409") (pin "+") (pinfunction "+_+") (pintype "passive"))
      (node (ref "J402") (pin "2") (pinfunction "2_2") (pintype "passive"))
      (node (ref "Q3") (pin "3") (pinfunction "C_3") (pintype "passive"))
      (node (ref "Q303") (pin "3") (pinfunction "C_3") (pintype "passive"))
      (node (ref "U1") (pin "4") (pinfunction "V+_4") (pintype "power_in"))
      (node (ref "U302") (pin "4") (pinfunction "V+_4") (pintype "power_in"))
      (node (ref "U401") (pin "3") (pinfunction "OUT_3") (pintype "passive"))
    )
    (net (code "123") (name "V-") (class "Default")
      (node (ref "C10") (pin "2") (pinfunction "2_2") (pintype "passive"))
      (node (ref "C104") (pin "2") (pinfunction "2_2") (pintype "passive"))
      (node (ref "C106") (pin "2") (pinfunction "2_2") (pintype "passive"))
      (node (ref "C108") (pin "2") (pinfunction "2_2") (pintype "passive"))
      (node (ref "C109") (pin "2") (pinfunction "2_2") (pintype "passive"))
      (node (ref "C110") (pin "2") (pinfunction "2_2") (pintype "passive"))
      (node (ref "C111") (pin "2") (pinfunction "2_2") (pintype "passive"))
      (node (ref "C12") (pin "2") (pinfunction "2_2") (pintype "passive"))
      (node (ref "C14") (pin "2") (pinfunction "2_2") (pintype "passive"))
      (node (ref "C15") (pin "2") (pinfunction "2_2") (pintype "passive"))
      (node (ref "C2") (pin "2") (pinfunction "2_2") (pintype "passive"))
      (node (ref "C201") (pin "2") (pinfunction "2_2") (pintype "passive"))
      (node (ref "C203") (pin "2") (pinfunction "2_2") (pintype "passive"))
      (node (ref "C205") (pin "2") (pinfunction "2_2") (pintype "passive"))
      (node (ref "C206") (pin "2") (pinfunction "2_2") (pintype "passive"))
      (node (ref "C207") (pin "2") (pinfunction "2_2") (pintype "passive"))
      (node (ref "C208") (pin "2") (pinfunction "2_2") (pintype "passive"))
      (node (ref "C21") (pin "2") (pinfunction "2_2") (pintype "passive"))
      (node (ref "C22") (pin "2") (pinfunction "2_2") (pintype "passive"))
      (node (ref "C23") (pin "2") (pinfunction "2_2") (pintype "passive"))
      (node (ref "C24") (pin "2") (pinfunction "2_2") (pintype "passive"))
      (node (ref "C25") (pin "2") (pinfunction "2_2") (pintype "passive"))
      (node (ref "C26") (pin "2") (pinfunction "2_2") (pintype "passive"))
      (node (ref "C27") (pin "2") (pinfunction "2_2") (pintype "passive"))
      (node (ref "C28") (pin "2") (pinfunction "2_2") (pintype "passive"))
      (node (ref "C29") (pin "2") (pinfunction "2_2") (pintype "passive"))
      (node (ref "C3") (pin "2") (pinfunction "2_2") (pintype "passive"))
      (node (ref "C301") (pin "2") (pinfunction "2_2") (pintype "passive"))
      (node (ref "C302") (pin "2") (pinfunction "2_2") (pintype "passive"))
      (node (ref "C303") (pin "2") (pinfunction "2_2") (pintype "passive"))
      (node (ref "C305") (pin "2") (pinfunction "2_2") (pintype "passive"))
      (node (ref "C31") (pin "-") (pinfunction "-_-") (pintype "passive"))
      (node (ref "C4") (pin "2") (pinfunction "2_2") (pintype "passive"))
      (node (ref "C401") (pin "-") (pinfunction "-_-") (pintype "passive"))
      (node (ref "C402") (pin "2") (pinfunction "2_2") (pintype "passive"))
      (node (ref "C403") (pin "2") (pinfunction "2_2") (pintype "passive"))
      (node (ref "C404") (pin "2") (pinfunction "2_2") (pintype "passive"))
      (node (ref "C405") (pin "2") (pinfunction "2_2") (pintype "passive"))
      (node (ref "C406") (pin "2") (pinfunction "2_2") (pintype "passive"))
      (node (ref "C407") (pin "2") (pinfunction "2_2") (pintype "passive"))
      (node (ref "C408") (pin "2") (pinfunction "2_2") (pintype "passive"))
      (node (ref "C409") (pin "-") (pinfunction "-_-") (pintype "passive"))
      (node (ref "C410") (pin "-") (pinfunction "-_-") (pintype "passive"))
      (node (ref "C411") (pin "2") (pinfunction "2_2") (pintype "passive"))
      (node (ref "C412") (pin "2") (pinfunction "2_2") (pintype "passive"))
      (node (ref "C413") (pin "2") (pinfunction "2_2") (pintype "passive"))
      (node (ref "C5") (pin "2") (pinfunction "2_2") (pintype "passive"))
      (node (ref "C6") (pin "2") (pinfunction "2_2") (pintype "passive"))
      (node (ref "C9") (pin "2") (pinfunction "2_2") (pintype "passive"))
      (node (ref "D1") (pin "A") (pinfunction "A1_A") (pintype "passive"))
      (node (ref "D401") (pin "A") (pinfunction "A1_A") (pintype "passive"))
      (node (ref "H401") (pin "B3,2") (pinfunction "MOUNT_B3,2") (pintype "passive"))
      (node (ref "H402") (pin "B3,2") (pinfunction "MOUNT_B3,2") (pintype "passive"))
      (node (ref "H403") (pin "B3,2") (pinfunction "MOUNT_B3,2") (pintype "passive"))
      (node (ref "H404") (pin "B3,2") (pinfunction "MOUNT_B3,2") (pintype "passive"))
      (node (ref "IC1") (pin "4") (pinfunction "V-_4") (pintype "power_in"))
      (node (ref "IC2") (pin "4") (pinfunction "V-_4") (pintype "power_in"))
      (node (ref "IC3") (pin "4") (pinfunction "V-_4") (pintype "power_in"))
      (node (ref "IC5") (pin "3") (pinfunction "GND_3") (pintype "power_in"))
      (node (ref "IC6") (pin "11") (pinfunction "CLK_11") (pintype "input"))
      (node (ref "IC6") (pin "12") (pinfunction "D_12") (pintype "input"))
      (node (ref "IC6") (pin "13") (pinfunction "CLR_13") (pintype "input"))
      (node (ref "IC6") (pin "7") (pinfunction "GND_7") (pintype "power_in"))
      (node (ref "IC7") (pin "3") (pinfunction "GND_3") (pintype "power_in"))
      (node (ref "J401") (pin "2") (pinfunction "2_2") (pintype "passive"))
      (node (ref "J402") (pin "1") (pinfunction "1_1") (pintype "passive"))
      (node (ref "LED402") (pin "K") (pinfunction "C_K") (pintype "passive"))
      (node (ref "Q2") (pin "2") (pinfunction "S_2") (pintype "passive"))
      (node (ref "Q301") (pin "2") (pinfunction "S_2") (pintype "passive"))
      (node (ref "Q302") (pin "3") (pinfunction "C_3") (pintype "passive"))
      (node (ref "Q4") (pin "3") (pinfunction "C_3") (pintype "passive"))
      (node (ref "R101") (pin "2") (pinfunction "2_2") (pintype "passive"))
      (node (ref "R102") (pin "2") (pinfunction "2_2") (pintype "passive"))
      (node (ref "R103") (pin "2") (pinfunction "2_2") (pintype "passive"))
      (node (ref "R106") (pin "2") (pinfunction "2_2") (pintype "passive"))
      (node (ref "R107") (pin "2") (pinfunction "2_2") (pintype "passive"))
      (node (ref "R11") (pin "2") (pinfunction "2_2") (pintype "passive"))
      (node (ref "R122") (pin "2") (pinfunction "2_2") (pintype "passive"))
      (node (ref "R123") (pin "2") (pinfunction "2_2") (pintype "passive"))
      (node (ref "R124") (pin "2") (pinfunction "2_2") (pintype "passive"))
      (node (ref "R125") (pin "2") (pinfunction "2_2") (pintype "passive"))
      (node (ref "R126") (pin "2") (pinfunction "2_2") (pintype "passive"))
      (node (ref "R127") (pin "2") (pinfunction "2_2") (pintype "passive"))
      (node (ref "R128") (pin "2") (pinfunction "2_2") (pintype "passive"))
      (node (ref "R129") (pin "2") (pinfunction "2_2") (pintype "passive"))
      (node (ref "R13") (pin "1") (pinfunction "A_1") (pintype "passive"))
      (node (ref "R15") (pin "2") (pinfunction "2_2") (pintype "passive"))
      (node (ref "R16") (pin "2") (pinfunction "2_2") (pintype "passive"))
      (node (ref "R18") (pin "2") (pinfunction "2_2") (pintype "passive"))
      (node (ref "R201") (pin "2") (pinfunction "2_2") (pintype "passive"))
      (node (ref "R202") (pin "2") (pinfunction "2_2") (pintype "passive"))
      (node (ref "R205") (pin "2") (pinfunction "2_2") (pintype "passive"))
      (node (ref "R206") (pin "2") (pinfunction "2_2") (pintype "passive"))
      (node (ref "R221") (pin "2") (pinfunction "2_2") (pintype "passive"))
      (node (ref "R222") (pin "2") (pinfunction "2_2") (pintype "passive"))
      (node (ref "R223") (pin "2") (pinfunction "2_2") (pintype "passive"))
      (node (ref "R224") (pin "2") (pinfunction "2_2") (pintype "passive"))
      (node (ref "R225") (pin "2") (pinfunction "2_2") (pintype "passive"))
      (node (ref "R226") (pin "2") (pinfunction "2_2") (pintype "passive"))
      (node (ref "R227") (pin "2") (pinfunction "2_2") (pintype "passive"))
      (node (ref "R228") (pin "2") (pinfunction "2_2") (pintype "passive"))
      (node (ref "R26") (pin "2") (pinfunction "2_2") (pintype "passive"))
      (node (ref "R30") (pin "2") (pinfunction "2_2") (pintype "passive"))
      (node (ref "R301") (pin "1") (pinfunction "A_1") (pintype "passive"))
      (node (ref "R311") (pin "2") (pinfunction "2_2") (pintype "passive"))
      (node (ref "R312") (pin "1") (pinfunction "1_1") (pintype "passive"))
      (node (ref "R33") (pin "1") (pinfunction "A_1") (pintype "passive"))
      (node (ref "R34") (pin "1") (pinfunction "A_1") (pintype "passive"))
      (node (ref "R39") (pin "1") (pinfunction "1_1") (pintype "passive"))
      (node (ref "R42") (pin "2") (pinfunction "2_2") (pintype "passive"))
      (node (ref "R50") (pin "2") (pinfunction "2_2") (pintype "passive"))
      (node (ref "R52") (pin "2") (pinfunction "2_2") (pintype "passive"))
      (node (ref "R56") (pin "2") (pinfunction "2_2") (pintype "passive"))
      (node (ref "R8") (pin "2") (pinfunction "2_2") (pintype "passive"))
      (node (ref "SW1") (pin "1") (pinfunction "G1_1") (pintype "passive"))
      (node (ref "SW1") (pin "3") (pinfunction "S1_3") (pintype "passive"))
      (node (ref "SW1") (pin "4") (pinfunction "G2_4") (pintype "passive"))
      (node (ref "SW2") (pin "1") (pinfunction "G1_1") (pintype "passive"))
      (node (ref "SW2") (pin "4") (pinfunction "G2_4") (pintype "passive"))
      (node (ref "T102") (pin "9") (pinfunction "F4_9") (pintype "passive"))
      (node (ref "TP1") (pin "GND") (pinfunction "GND1_GND") (pintype "power_in"))
      (node (ref "TP10") (pin "GND") (pinfunction "GND1_GND") (pintype "power_in"))
      (node (ref "TP11") (pin "GND") (pinfunction "GND1_GND") (pintype "power_in"))
      (node (ref "TP12") (pin "GND") (pinfunction "GND1_GND") (pintype "power_in"))
      (node (ref "TP13") (pin "GND") (pinfunction "GND1_GND") (pintype "power_in"))
      (node (ref "TP14") (pin "GND") (pinfunction "GND1_GND") (pintype "power_in"))
      (node (ref "TP18") (pin "GND") (pinfunction "GND1_GND") (pintype "power_in"))
      (node (ref "TP19") (pin "GND") (pinfunction "GND1_GND") (pintype "power_in"))
      (node (ref "TP2") (pin "GND") (pinfunction "GND1_GND") (pintype "power_in"))
      (node (ref "TP20") (pin "GND") (pinfunction "GND1_GND") (pintype "power_in"))
      (node (ref "TP21") (pin "GND") (pinfunction "GND1_GND") (pintype "power_in"))
      (node (ref "TP22") (pin "GND") (pinfunction "GND1_GND") (pintype "power_in"))
      (node (ref "TP23") (pin "GND") (pinfunction "GND1_GND") (pintype "power_in"))
      (node (ref "TP25") (pin "GND") (pinfunction "GND1_GND") (pintype "power_in"))
      (node (ref "TP27") (pin "GND") (pinfunction "GND1_GND") (pintype "power_in"))
      (node (ref "TP3") (pin "GND") (pinfunction "GND1_GND") (pintype "power_in"))
      (node (ref "TP4") (pin "GND") (pinfunction "GND1_GND") (pintype "power_in"))
      (node (ref "TP5") (pin "GND") (pinfunction "GND1_GND") (pintype "power_in"))
      (node (ref "TP6") (pin "GND") (pinfunction "GND1_GND") (pintype "power_in"))
      (node (ref "TP7") (pin "GND") (pinfunction "GND1_GND") (pintype "power_in"))
      (node (ref "TP8") (pin "GND") (pinfunction "GND1_GND") (pintype "power_in"))
      (node (ref "TP9") (pin "GND") (pinfunction "GND1_GND") (pintype "power_in"))
      (node (ref "U1") (pin "10") (pinfunction "+IN_10") (pintype "input"))
      (node (ref "U1") (pin "11") (pinfunction "V-_11") (pintype "power_in"))
      (node (ref "U2") (pin "2") (pinfunction "A_2") (pintype "passive"))
      (node (ref "U302") (pin "11") (pinfunction "V-_11") (pintype "power_in"))
      (node (ref "U401") (pin "2") (pinfunction "GND_2") (pintype "input"))
      (node (ref "U402") (pin "2") (pinfunction "GND_2") (pintype "input"))
      (node (ref "X1") (pin "2") (pinfunction "2_2") (pintype "passive"))
      (node (ref "X2") (pin "2") (pinfunction "2_2") (pintype "passive"))
      (node (ref "X4") (pin "2") (pinfunction "2_2") (pintype "passive"))
      (node (ref "X402") (pin "P1") (pinfunction "P$1_P1") (pintype "bidirectional"))
      (node (ref "X402") (pin "P2") (pinfunction "P$2_P2") (pintype "bidirectional"))
    )
    (net (code "124") (name "VB") (class "Default")
      (node (ref "C116") (pin "1") (pinfunction "1_1") (pintype "passive"))
      (node (ref "C117") (pin "1") (pinfunction "1_1") (pintype "passive"))
      (node (ref "C29") (pin "1") (pinfunction "1_1") (pintype "passive"))
      (node (ref "C408") (pin "1") (pinfunction "1_1") (pintype "passive"))
      (node (ref "C411") (pin "1") (pinfunction "1_1") (pintype "passive"))
      (node (ref "C412") (pin "1") (pinfunction "1_1") (pintype "passive"))
      (node (ref "C413") (pin "1") (pinfunction "1_1") (pintype "passive"))
      (node (ref "C8") (pin "1") (pinfunction "1_1") (pintype "passive"))
      (node (ref "L1") (pin "2") (pinfunction "2_2") (pintype "passive"))
      (node (ref "L103") (pin "2") (pinfunction "2_2") (pintype "passive"))
      (node (ref "L104") (pin "2") (pinfunction "2_2") (pintype "passive"))
      (node (ref "L402") (pin "2") (pinfunction "2_2") (pintype "passive"))
      (node (ref "R132") (pin "1") (pinfunction "1_1") (pintype "passive"))
      (node (ref "R404") (pin "2") (pinfunction "2_2") (pintype "passive"))
      (node (ref "R405") (pin "2") (pinfunction "2_2") (pintype "passive"))
      (node (ref "T1") (pin "10") (pinfunction "F3_10") (pintype "passive"))
    )
    (net (code "125") (name "VB_CONN") (class "Default")
      (node (ref "F401") (pin "1") (pinfunction "1_1") (pintype "passive"))
      (node (ref "J401") (pin "1") (pinfunction "1_1") (pintype "passive"))
    )
    (net (code "126") (name "VB_FUSED") (class "Default")
      (node (ref "D401") (pin "K") (pinfunction "C1_K") (pintype "passive"))
      (node (ref "F401") (pin "2") (pinfunction "2_2") (pintype "passive"))
      (node (ref "R401") (pin "1") (pinfunction "1_1") (pintype "passive"))
    )
    (net (code "127") (name "VB_ICL") (class "Default")
      (node (ref "C401") (pin "+") (pinfunction "+_+") (pintype "passive"))
      (node (ref "C402") (pin "1") (pinfunction "1_1") (pintype "passive"))
      (node (ref "L401") (pin "1") (pinfunction "1_1") (pintype "passive"))
      (node (ref "Q6") (pin "D") (pinfunction "C_D") (pintype "passive"))
      (node (ref "R401") (pin "2") (pinfunction "2_2") (pintype "passive"))
      (node (ref "R55") (pin "1") (pinfunction "1_1") (pintype "passive"))
    )
    (net (code "128") (name "unconnected-(H1-MOUNT-PadB3,2)") (class "Default")
      (node (ref "H1") (pin "B3,2") (pinfunction "MOUNT_B3,2") (pintype "passive"))
    )
    (net (code "129") (name "unconnected-(H2-MOUNT-PadB3,2)") (class "Default")
      (node (ref "H2") (pin "B3,2") (pinfunction "MOUNT_B3,2") (pintype "passive"))
    )
    (net (code "130") (name "unconnected-(IC1-ON1-Pad1)") (class "Default")
      (node (ref "IC1") (pin "1") (pinfunction "ON1_1") (pintype "passive"))
    )
    (net (code "131") (name "unconnected-(IC1-ON2-Pad5)") (class "Default")
      (node (ref "IC1") (pin "5") (pinfunction "ON2_5") (pintype "passive"))
    )
    (net (code "132") (name "unconnected-(IC1-OPT-Pad8)") (class "Default")
      (node (ref "IC1") (pin "8") (pinfunction "OPT_8") (pintype "passive"))
    )
    (net (code "133") (name "unconnected-(IC2-ON1-Pad1)") (class "Default")
      (node (ref "IC2") (pin "1") (pinfunction "ON1_1") (pintype "passive"))
    )
    (net (code "134") (name "unconnected-(IC2-ON2-Pad5)") (class "Default")
      (node (ref "IC2") (pin "5") (pinfunction "ON2_5") (pintype "passive"))
    )
    (net (code "135") (name "unconnected-(IC2-OPT-Pad8)") (class "Default")
      (node (ref "IC2") (pin "8") (pinfunction "OPT_8") (pintype "passive"))
    )
    (net (code "136") (name "unconnected-(IC6B-Q-Pad9)") (class "Default")
      (node (ref "IC6") (pin "9") (pinfunction "Q_9") (pintype "output"))
    )
    (net (code "137") (name "unconnected-(IC6B-~{Q}-Pad8)") (class "Default")
      (node (ref "IC6") (pin "8") (pinfunction "~{Q}_8") (pintype "output"))
    )
    (net (code "138") (name "unconnected-(J402-Pad4)") (class "Default")
      (node (ref "J402") (pin "4") (pinfunction "4_4") (pintype "passive"))
    )
    (net (code "139") (name "~{BLANK_GATED}") (class "Default")
      (node (ref "IC5") (pin "4") (pinfunction "O_4") (pintype "output"))
      (node (ref "Q2") (pin "1") (pinfunction "G_1") (pintype "passive"))
      (node (ref "Q301") (pin "1") (pinfunction "G_1") (pintype "passive"))
      (node (ref "TP14") (pin "TP") (pinfunction "1_TP") (pintype "passive"))
    )
    (net (code "140") (name "~{FAULT}") (class "Default")
      (node (ref "IC3") (pin "1") (pinfunction "OUT_1") (pintype "output"))
      (node (ref "IC3") (pin "7") (pinfunction "OUT_7") (pintype "output"))
      (node (ref "IC6") (pin "1") (pinfunction "CLR_1") (pintype "input"))
      (node (ref "R10") (pin "2") (pinfunction "2_2") (pintype "passive"))
      (node (ref "R2") (pin "2") (pinfunction "2_2") (pintype "passive"))
      (node (ref "R5") (pin "2") (pinfunction "2_2") (pintype "passive"))
      (node (ref "SW1") (pin "2") (pinfunction "P1_2") (pintype "passive"))
    )
    (net (code "141") (name "~{READY}") (class "Default")
      (node (ref "IC6") (pin "6") (pinfunction "~{Q}_6") (pintype "output"))
      (node (ref "R12") (pin "2") (pinfunction "2_2") (pintype "passive"))
    )
  )
)
